# camera.net
KiCad netlist of a schematic drawn in EAGLE
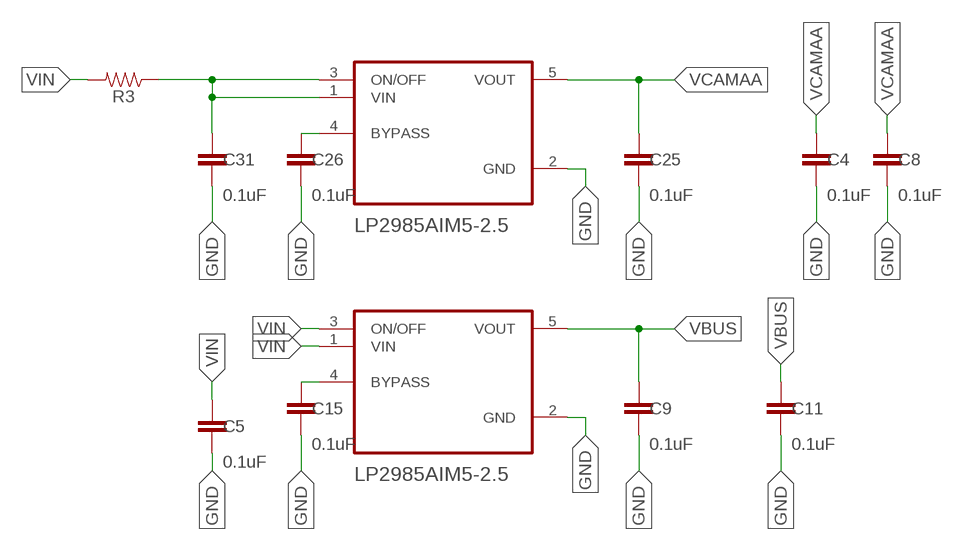
[diagram p0: schematic, sheet 1, part 1 of 3]
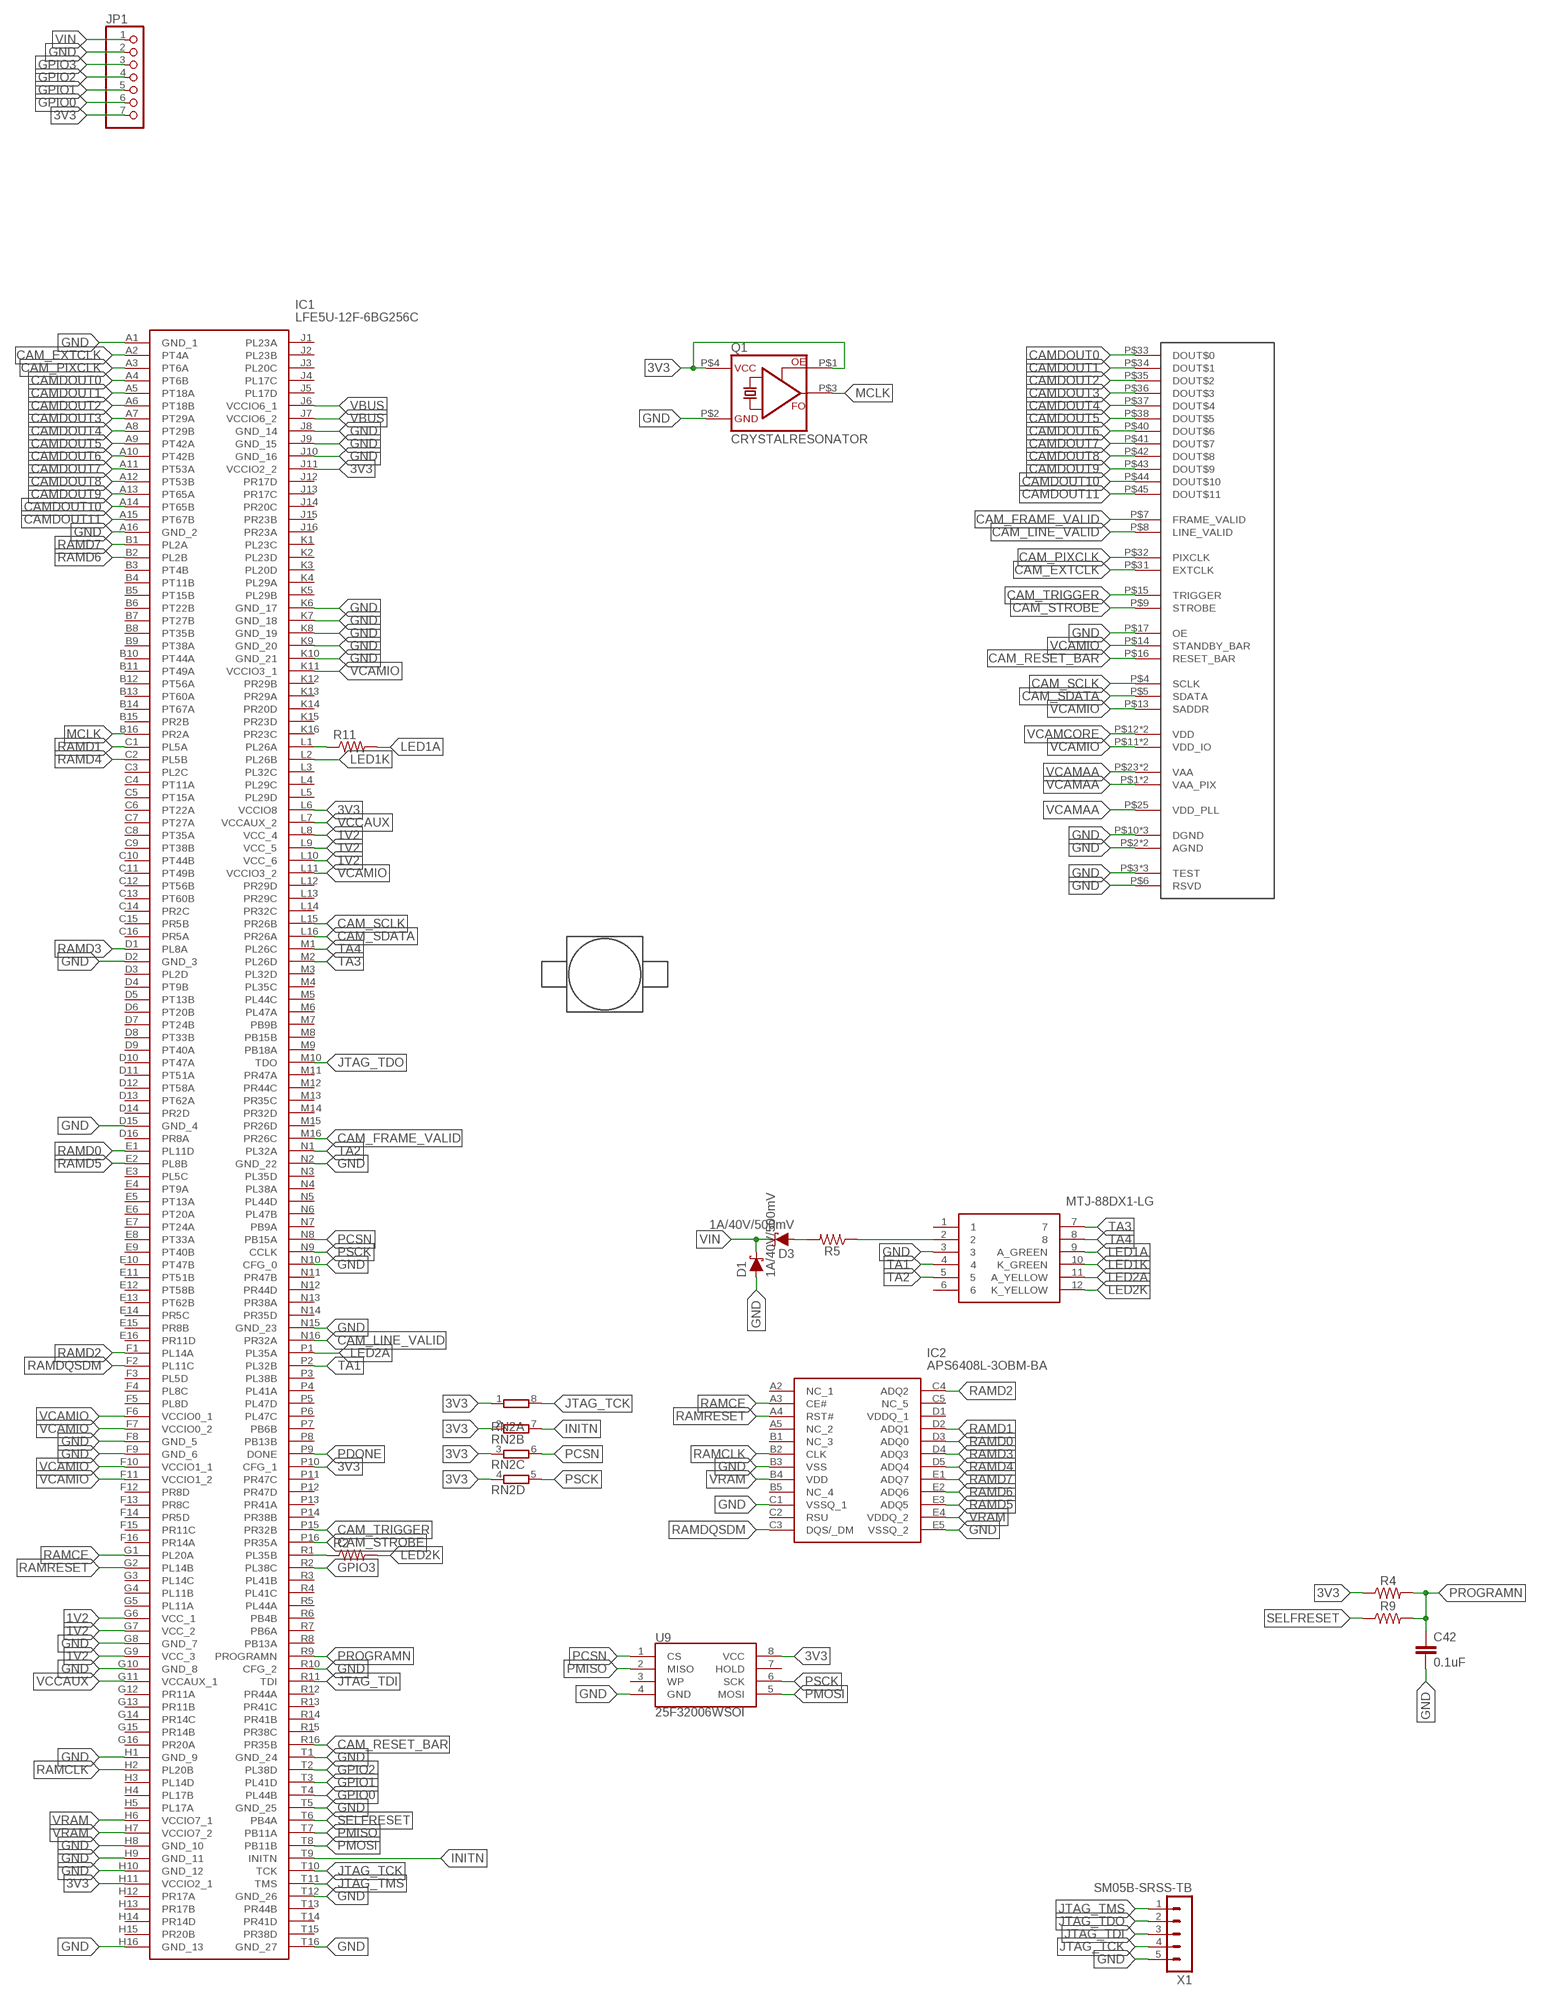
[diagram p1: schematic, sheet 1, part 2 of 3]
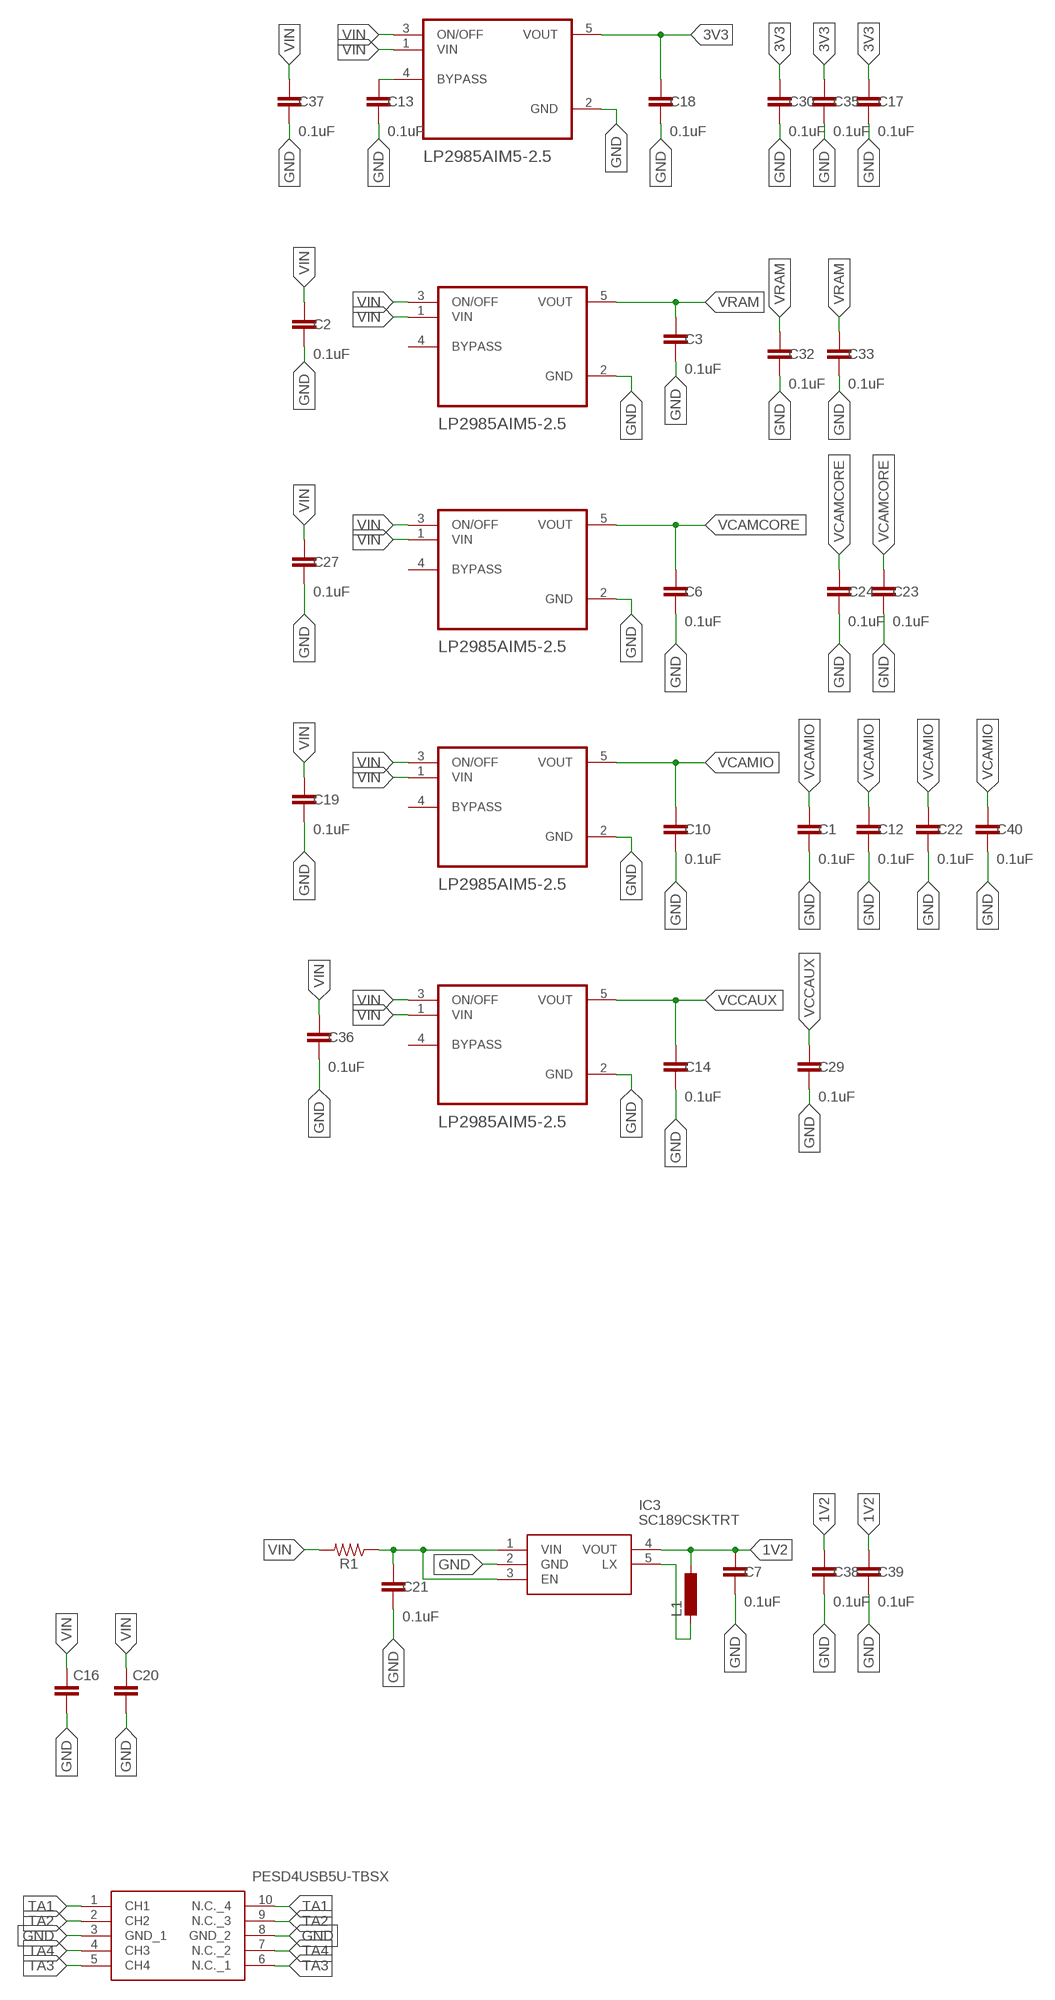
[diagram p2: schematic, sheet 1, part 3 of 3]

(export (version "E")
  (design (tool "Eeschema 10.0.6"))
  (components
    (comp (ref "C1")
      (value "0.1uF")
      (footprint "eagle-import:0603")
      (libsource (lib "eagle-import") (part "0.1UF-0603-25V-5%"))
    )
    (comp (ref "C2")
      (value "0.1uF")
      (footprint "eagle-import:0603")
      (libsource (lib "eagle-import") (part "0.1UF-0603-25V-5%"))
    )
    (comp (ref "C3")
      (value "0.1uF")
      (footprint "eagle-import:0603")
      (libsource (lib "eagle-import") (part "0.1UF-0603-25V-5%"))
    )
    (comp (ref "C4")
      (value "0.1uF")
      (footprint "eagle-import:0603")
      (libsource (lib "eagle-import") (part "0.1UF-0603-25V-5%"))
    )
    (comp (ref "C5")
      (value "0.1uF")
      (footprint "eagle-import:0603")
      (libsource (lib "eagle-import") (part "0.1UF-0603-25V-5%"))
    )
    (comp (ref "C6")
      (value "0.1uF")
      (footprint "eagle-import:0603")
      (libsource (lib "eagle-import") (part "0.1UF-0603-25V-5%"))
    )
    (comp (ref "C7")
      (value "0.1uF")
      (footprint "eagle-import:0603")
      (libsource (lib "eagle-import") (part "0.1UF-0603-25V-5%"))
    )
    (comp (ref "C8")
      (value "0.1uF")
      (footprint "eagle-import:0603")
      (libsource (lib "eagle-import") (part "0.1UF-0603-25V-5%"))
    )
    (comp (ref "C9")
      (value "0.1uF")
      (footprint "eagle-import:0603")
      (libsource (lib "eagle-import") (part "0.1UF-0603-25V-5%"))
    )
    (comp (ref "C10")
      (value "0.1uF")
      (footprint "eagle-import:0603")
      (libsource (lib "eagle-import") (part "0.1UF-0603-25V-5%"))
    )
    (comp (ref "C11")
      (value "0.1uF")
      (footprint "eagle-import:0603")
      (libsource (lib "eagle-import") (part "0.1UF-0603-25V-5%"))
    )
    (comp (ref "C12")
      (value "0.1uF")
      (footprint "eagle-import:0603")
      (libsource (lib "eagle-import") (part "0.1UF-0603-25V-5%"))
    )
    (comp (ref "C13")
      (value "0.1uF")
      (footprint "eagle-import:0603")
      (libsource (lib "eagle-import") (part "0.1UF-0603-25V-5%"))
    )
    (comp (ref "C14")
      (value "0.1uF")
      (footprint "eagle-import:0603")
      (libsource (lib "eagle-import") (part "0.1UF-0603-25V-5%"))
    )
    (comp (ref "C15")
      (value "0.1uF")
      (footprint "eagle-import:0603")
      (libsource (lib "eagle-import") (part "0.1UF-0603-25V-5%"))
    )
    (comp (ref "C16")
      (value "C-EUC1812")
      (footprint "eagle-import:C1812")
      (libsource (lib "eagle-import") (part "C-EUC1812"))
    )
    (comp (ref "C17")
      (value "0.1uF")
      (footprint "eagle-import:0603")
      (libsource (lib "eagle-import") (part "0.1UF-0603-25V-5%"))
    )
    (comp (ref "C18")
      (value "0.1uF")
      (footprint "eagle-import:0603")
      (libsource (lib "eagle-import") (part "0.1UF-0603-25V-5%"))
    )
    (comp (ref "C19")
      (value "0.1uF")
      (footprint "eagle-import:0603")
      (libsource (lib "eagle-import") (part "0.1UF-0603-25V-5%"))
    )
    (comp (ref "C20")
      (value "C-EUC1812")
      (footprint "eagle-import:C1812")
      (libsource (lib "eagle-import") (part "C-EUC1812"))
    )
    (comp (ref "C21")
      (value "0.1uF")
      (footprint "eagle-import:0603")
      (libsource (lib "eagle-import") (part "0.1UF-0603-25V-5%"))
    )
    (comp (ref "C22")
      (value "0.1uF")
      (footprint "eagle-import:0603")
      (libsource (lib "eagle-import") (part "0.1UF-0603-25V-5%"))
    )
    (comp (ref "C23")
      (value "0.1uF")
      (footprint "eagle-import:0603")
      (libsource (lib "eagle-import") (part "0.1UF-0603-25V-5%"))
    )
    (comp (ref "C24")
      (value "0.1uF")
      (footprint "eagle-import:0603")
      (libsource (lib "eagle-import") (part "0.1UF-0603-25V-5%"))
    )
    (comp (ref "C25")
      (value "0.1uF")
      (footprint "eagle-import:0603")
      (libsource (lib "eagle-import") (part "0.1UF-0603-25V-5%"))
    )
    (comp (ref "C26")
      (value "0.1uF")
      (footprint "eagle-import:0603")
      (libsource (lib "eagle-import") (part "0.1UF-0603-25V-5%"))
    )
    (comp (ref "C27")
      (value "0.1uF")
      (footprint "eagle-import:0603")
      (libsource (lib "eagle-import") (part "0.1UF-0603-25V-5%"))
    )
    (comp (ref "C29")
      (value "0.1uF")
      (footprint "eagle-import:0603")
      (libsource (lib "eagle-import") (part "0.1UF-0603-25V-5%"))
    )
    (comp (ref "C30")
      (value "0.1uF")
      (footprint "eagle-import:0603")
      (libsource (lib "eagle-import") (part "0.1UF-0603-25V-5%"))
    )
    (comp (ref "C31")
      (value "0.1uF")
      (footprint "eagle-import:0603")
      (libsource (lib "eagle-import") (part "0.1UF-0603-25V-5%"))
    )
    (comp (ref "C32")
      (value "0.1uF")
      (footprint "eagle-import:0603")
      (libsource (lib "eagle-import") (part "0.1UF-0603-25V-5%"))
    )
    (comp (ref "C33")
      (value "0.1uF")
      (footprint "eagle-import:0603")
      (libsource (lib "eagle-import") (part "0.1UF-0603-25V-5%"))
    )
    (comp (ref "C35")
      (value "0.1uF")
      (footprint "eagle-import:0603")
      (libsource (lib "eagle-import") (part "0.1UF-0603-25V-5%"))
    )
    (comp (ref "C36")
      (value "0.1uF")
      (footprint "eagle-import:0603")
      (libsource (lib "eagle-import") (part "0.1UF-0603-25V-5%"))
    )
    (comp (ref "C37")
      (value "0.1uF")
      (footprint "eagle-import:0603")
      (libsource (lib "eagle-import") (part "0.1UF-0603-25V-5%"))
    )
    (comp (ref "C38")
      (value "0.1uF")
      (footprint "eagle-import:0603")
      (libsource (lib "eagle-import") (part "0.1UF-0603-25V-5%"))
    )
    (comp (ref "C39")
      (value "0.1uF")
      (footprint "eagle-import:0603")
      (libsource (lib "eagle-import") (part "0.1UF-0603-25V-5%"))
    )
    (comp (ref "C40")
      (value "0.1uF")
      (footprint "eagle-import:0603")
      (libsource (lib "eagle-import") (part "0.1UF-0603-25V-5%"))
    )
    (comp (ref "C42")
      (value "0.1uF")
      (footprint "eagle-import:0603")
      (libsource (lib "eagle-import") (part "0.1UF-0603-25V-5%"))
    )
    (comp (ref "D1")
      (value "1A/40V/500mV")
      (footprint "eagle-import:SMA-DIODE")
      (libsource (lib "eagle-import") (part "DIODE-SCHOTTKY-SS14"))
    )
    (comp (ref "D3")
      (value "1A/40V/500mV")
      (footprint "eagle-import:SMA-DIODE")
      (libsource (lib "eagle-import") (part "DIODE-SCHOTTKY-SS14"))
    )
    (comp (ref "D10")
      (value "PESD4USB5U-TBSX")
      (footprint "eagle-import:SON50P100X250X80-10N")
      (fields (field (name "MOUSER_PART_NUMBER") "771-PESD4USB5U-TBSX"))
      (libsource (lib "eagle-import") (part "PESD4USB5U-TBSX"))
    )
    (comp (ref "IC1")
      (value "LFE5U-12F-6BG256C")
      (footprint "eagle-import:BGA256C80P16X16_1400X1400X170")
      (fields (field (name "MF") "Lattice Semiconductor"))
      (libsource (lib "eagle-import") (part "LFE5U-12F-6BG256C"))
    )
    (comp (ref "IC2")
      (value "APS6408L-3OBM-BA")
      (footprint "eagle-import:BGA24C100P5X5_600X800X120")
      (fields (field (name "MOUSER_PART_NUMBER") "878-APS6408L-3OBM-BA"))
      (libsource (lib "eagle-import") (part "APS6408L-3OBM-BA"))
    )
    (comp (ref "IC3")
      (value "SC189CSKTRT")
      (footprint "eagle-import:SOT95P280X145-5N")
      (fields (field (name "MOUSER_PART_NUMBER") "947-SC189CSKTRT"))
      (libsource (lib "eagle-import") (part "SC189CSKTRT"))
    )
    (comp (ref "J1")
      (value "MTJ-88DX1-LG")
      (footprint "eagle-import:MTJ88DX1LG")
      (libsource (lib "eagle-import") (part "MTJ-88DX1-LG"))
    )
    (comp (ref "JP1")
      (value "PINHD-1X7M")
      (footprint "eagle-import:1X07M")
      (libsource (lib "eagle-import") (part "PINHD-1X7M"))
    )
    (comp (ref "L1")
      (value "L-EUL3230M")
      (footprint "eagle-import:L3230M")
      (libsource (lib "eagle-import") (part "L-EUL3230M"))
    )
    (comp (ref "Q1")
      (value "CRYSTALRESONATOR")
      (footprint "eagle-import:XO53X")
      (libsource (lib "eagle-import") (part "CRYSTALRESONATOR"))
    )
    (comp (ref "R1")
      (value "RESISTOR0603")
      (footprint "eagle-import:0603")
      (libsource (lib "eagle-import") (part "RESISTOR0603"))
    )
    (comp (ref "R2")
      (value "RESISTOR0603")
      (footprint "eagle-import:0603")
      (libsource (lib "eagle-import") (part "RESISTOR0603"))
    )
    (comp (ref "R3")
      (value "RESISTOR0603")
      (footprint "eagle-import:0603")
      (libsource (lib "eagle-import") (part "RESISTOR0603"))
    )
    (comp (ref "R4")
      (value "RESISTOR0603")
      (footprint "eagle-import:0603")
      (libsource (lib "eagle-import") (part "RESISTOR0603"))
    )
    (comp (ref "R5")
      (value "RESISTOR0805")
      (footprint "eagle-import:0805")
      (libsource (lib "eagle-import") (part "RESISTOR0805"))
    )
    (comp (ref "R9")
      (value "RESISTOR0603")
      (footprint "eagle-import:0603")
      (libsource (lib "eagle-import") (part "RESISTOR0603"))
    )
    (comp (ref "R11")
      (value "RESISTOR0603")
      (footprint "eagle-import:0603")
      (libsource (lib "eagle-import") (part "RESISTOR0603"))
    )
    (comp (ref "RN2")
      (value "4R-NEXBV8V")
      (footprint "eagle-import:EXBV8V")
      (libsource (lib "eagle-import") (part "4R-NEXBV8V"))
    )
    (comp (ref "U$1")
      (value "LENS-HOLDER")
      (footprint "eagle-import:LENS-HOLDER")
      (libsource (lib "eagle-import") (part "LENS-HOLDER"))
    )
    (comp (ref "U$2")
      (value "MT9P001")
      (footprint "eagle-import:MT9P001")
      (libsource (lib "eagle-import") (part "MT9P001"))
    )
    (comp (ref "U1")
      (value "LP2985AIM5-2.5")
      (footprint "eagle-import:SOT95P280X145-5N")
      (fields (field (name "MF") "Texas Instruments") (field (name "MP") "LP2985AIM5-2.5/NOPB"))
      (libsource (lib "eagle-import") (part "LP2985AIM5-2.5"))
    )
    (comp (ref "U2")
      (value "LP2985AIM5-2.5")
      (footprint "eagle-import:SOT95P280X145-5N")
      (fields (field (name "MF") "Texas Instruments") (field (name "MP") "LP2985AIM5-2.5/NOPB"))
      (libsource (lib "eagle-import") (part "LP2985AIM5-2.5"))
    )
    (comp (ref "U3")
      (value "LP2985AIM5-2.5")
      (footprint "eagle-import:SOT95P280X145-5N")
      (fields (field (name "MF") "Texas Instruments") (field (name "MP") "LP2985AIM5-2.5/NOPB"))
      (libsource (lib "eagle-import") (part "LP2985AIM5-2.5"))
    )
    (comp (ref "U4")
      (value "LP2985AIM5-2.5")
      (footprint "eagle-import:SOT95P280X145-5N")
      (fields (field (name "MF") "Texas Instruments") (field (name "MP") "LP2985AIM5-2.5/NOPB"))
      (libsource (lib "eagle-import") (part "LP2985AIM5-2.5"))
    )
    (comp (ref "U5")
      (value "LP2985AIM5-2.5")
      (footprint "eagle-import:SOT95P280X145-5N")
      (fields (field (name "MF") "Texas Instruments") (field (name "MP") "LP2985AIM5-2.5/NOPB"))
      (libsource (lib "eagle-import") (part "LP2985AIM5-2.5"))
    )
    (comp (ref "U6")
      (value "LP2985AIM5-2.5")
      (footprint "eagle-import:SOT95P280X145-5N")
      (fields (field (name "MF") "Texas Instruments") (field (name "MP") "LP2985AIM5-2.5/NOPB"))
      (libsource (lib "eagle-import") (part "LP2985AIM5-2.5"))
    )
    (comp (ref "U8")
      (value "LP2985AIM5-2.5")
      (footprint "eagle-import:SOT95P280X145-5N")
      (fields (field (name "MF") "Texas Instruments") (field (name "MP") "LP2985AIM5-2.5/NOPB"))
      (libsource (lib "eagle-import") (part "LP2985AIM5-2.5"))
    )
    (comp (ref "U9")
      (value "25F32006WSOI")
      (footprint "eagle-import:SO08-EIAJ")
      (libsource (lib "eagle-import") (part "SPI_FLASH-X25XXSMD1"))
    )
    (comp (ref "X1")
      (value "SM05B-SRSS-TB")
      (footprint "eagle-import:SM05B-SRSS-TB")
      (libsource (lib "eagle-import") (part "SM05B-SRSS-TB"))
    )
  )
  (nets
    (net (code "1") (name "1V2") (class "Default")
      (node (ref "C38") (pin "1") (pinfunction "1_1") (pintype "passive"))
      (node (ref "C39") (pin "1") (pinfunction "1_1") (pintype "passive"))
      (node (ref "C7") (pin "1") (pinfunction "1_1") (pintype "passive"))
      (node (ref "IC1") (pin "G6") (pinfunction "VCC_1_G6") (pintype "bidirectional"))
      (node (ref "IC1") (pin "G7") (pinfunction "VCC_2_G7") (pintype "bidirectional"))
      (node (ref "IC1") (pin "G9") (pinfunction "VCC_3_G9") (pintype "bidirectional"))
      (node (ref "IC1") (pin "L10") (pinfunction "VCC_6_L10") (pintype "bidirectional"))
      (node (ref "IC1") (pin "L8") (pinfunction "VCC_4_L8") (pintype "bidirectional"))
      (node (ref "IC1") (pin "L9") (pinfunction "VCC_5_L9") (pintype "bidirectional"))
      (node (ref "IC3") (pin "4") (pinfunction "VOUT_4") (pintype "bidirectional"))
      (node (ref "L1") (pin "1") (pinfunction "1_1") (pintype "passive"))
    )
    (net (code "2") (name "3V3") (class "Default")
      (node (ref "C17") (pin "1") (pinfunction "1_1") (pintype "passive"))
      (node (ref "C18") (pin "1") (pinfunction "1_1") (pintype "passive"))
      (node (ref "C30") (pin "1") (pinfunction "1_1") (pintype "passive"))
      (node (ref "C35") (pin "1") (pinfunction "1_1") (pintype "passive"))
      (node (ref "IC1") (pin "H11") (pinfunction "VCCIO2_1_H11") (pintype "bidirectional"))
      (node (ref "IC1") (pin "J11") (pinfunction "VCCIO2_2_J11") (pintype "bidirectional"))
      (node (ref "IC1") (pin "L6") (pinfunction "VCCIO8_L6") (pintype "bidirectional"))
      (node (ref "IC1") (pin "P10") (pinfunction "CFG_1_P10") (pintype "bidirectional"))
      (node (ref "JP1") (pin "7") (pinfunction "7_7") (pintype "passive"))
      (node (ref "Q1") (pin "P$1") (pinfunction "OE_P$1") (pintype "input"))
      (node (ref "Q1") (pin "P$4") (pinfunction "VCC_P$4") (pintype "power_in"))
      (node (ref "R4") (pin "1") (pinfunction "1_1") (pintype "passive"))
      (node (ref "RN2") (pin "1") (pinfunction "1_1") (pintype "passive"))
      (node (ref "RN2") (pin "2") (pinfunction "1_2") (pintype "passive"))
      (node (ref "RN2") (pin "3") (pinfunction "1_3") (pintype "passive"))
      (node (ref "RN2") (pin "4") (pinfunction "1_4") (pintype "passive"))
      (node (ref "U2") (pin "5") (pinfunction "VOUT_5") (pintype "output"))
      (node (ref "U9") (pin "8") (pinfunction "VCC_8") (pintype "power_in"))
    )
    (net (code "3") (name "CAMDOUT0") (class "Default")
      (node (ref "IC1") (pin "A4") (pinfunction "PT6B_A4") (pintype "bidirectional"))
      (node (ref "U$2") (pin "P$33") (pinfunction "DOUT$0_P$33") (pintype "output"))
    )
    (net (code "4") (name "CAMDOUT1") (class "Default")
      (node (ref "IC1") (pin "A5") (pinfunction "PT18A_A5") (pintype "bidirectional"))
      (node (ref "U$2") (pin "P$34") (pinfunction "DOUT$1_P$34") (pintype "output"))
    )
    (net (code "5") (name "CAMDOUT2") (class "Default")
      (node (ref "IC1") (pin "A6") (pinfunction "PT18B_A6") (pintype "bidirectional"))
      (node (ref "U$2") (pin "P$35") (pinfunction "DOUT$2_P$35") (pintype "output"))
    )
    (net (code "6") (name "CAMDOUT3") (class "Default")
      (node (ref "IC1") (pin "A7") (pinfunction "PT29A_A7") (pintype "bidirectional"))
      (node (ref "U$2") (pin "P$36") (pinfunction "DOUT$3_P$36") (pintype "output"))
    )
    (net (code "7") (name "CAMDOUT4") (class "Default")
      (node (ref "IC1") (pin "A8") (pinfunction "PT29B_A8") (pintype "bidirectional"))
      (node (ref "U$2") (pin "P$37") (pinfunction "DOUT$4_P$37") (pintype "output"))
    )
    (net (code "8") (name "CAMDOUT5") (class "Default")
      (node (ref "IC1") (pin "A9") (pinfunction "PT42A_A9") (pintype "bidirectional"))
      (node (ref "U$2") (pin "P$38") (pinfunction "DOUT$5_P$38") (pintype "output"))
    )
    (net (code "9") (name "CAMDOUT6") (class "Default")
      (node (ref "IC1") (pin "A10") (pinfunction "PT42B_A10") (pintype "bidirectional"))
      (node (ref "U$2") (pin "P$40") (pinfunction "DOUT$6_P$40") (pintype "output"))
    )
    (net (code "10") (name "CAMDOUT7") (class "Default")
      (node (ref "IC1") (pin "A11") (pinfunction "PT53A_A11") (pintype "bidirectional"))
      (node (ref "U$2") (pin "P$41") (pinfunction "DOUT$7_P$41") (pintype "output"))
    )
    (net (code "11") (name "CAMDOUT8") (class "Default")
      (node (ref "IC1") (pin "A12") (pinfunction "PT53B_A12") (pintype "bidirectional"))
      (node (ref "U$2") (pin "P$42") (pinfunction "DOUT$8_P$42") (pintype "output"))
    )
    (net (code "12") (name "CAMDOUT9") (class "Default")
      (node (ref "IC1") (pin "A13") (pinfunction "PT65A_A13") (pintype "bidirectional"))
      (node (ref "U$2") (pin "P$43") (pinfunction "DOUT$9_P$43") (pintype "output"))
    )
    (net (code "13") (name "CAMDOUT10") (class "Default")
      (node (ref "IC1") (pin "A14") (pinfunction "PT65B_A14") (pintype "bidirectional"))
      (node (ref "U$2") (pin "P$44") (pinfunction "DOUT$10_P$44") (pintype "output"))
    )
    (net (code "14") (name "CAMDOUT11") (class "Default")
      (node (ref "IC1") (pin "A15") (pinfunction "PT67B_A15") (pintype "bidirectional"))
      (node (ref "U$2") (pin "P$45") (pinfunction "DOUT$11_P$45") (pintype "output"))
    )
    (net (code "15") (name "CAM_EXTCLK") (class "Default")
      (node (ref "IC1") (pin "A2") (pinfunction "PT4A_A2") (pintype "bidirectional"))
      (node (ref "U$2") (pin "P$31") (pinfunction "EXTCLK_P$31") (pintype "bidirectional"))
    )
    (net (code "16") (name "CAM_FRAME_VALID") (class "Default")
      (node (ref "IC1") (pin "M16") (pinfunction "PR26C_M16") (pintype "bidirectional"))
      (node (ref "U$2") (pin "P$7") (pinfunction "FRAME_VALID_P$7") (pintype "bidirectional"))
    )
    (net (code "17") (name "CAM_LINE_VALID") (class "Default")
      (node (ref "IC1") (pin "N16") (pinfunction "PR32A_N16") (pintype "bidirectional"))
      (node (ref "U$2") (pin "P$8") (pinfunction "LINE_VALID_P$8") (pintype "bidirectional"))
    )
    (net (code "18") (name "CAM_PIXCLK") (class "Default")
      (node (ref "IC1") (pin "A3") (pinfunction "PT6A_A3") (pintype "bidirectional"))
      (node (ref "U$2") (pin "P$32") (pinfunction "PIXCLK_P$32") (pintype "bidirectional"))
    )
    (net (code "19") (name "CAM_RESET_BAR") (class "Default")
      (node (ref "IC1") (pin "R16") (pinfunction "PR35B_R16") (pintype "bidirectional"))
      (node (ref "U$2") (pin "P$16") (pinfunction "RESET_BAR_P$16") (pintype "bidirectional"))
    )
    (net (code "20") (name "CAM_SCLK") (class "Default")
      (node (ref "IC1") (pin "L15") (pinfunction "PR26B_L15") (pintype "bidirectional"))
      (node (ref "U$2") (pin "P$4") (pinfunction "SCLK_P$4") (pintype "bidirectional"))
    )
    (net (code "21") (name "CAM_SDATA") (class "Default")
      (node (ref "IC1") (pin "L16") (pinfunction "PR26A_L16") (pintype "bidirectional"))
      (node (ref "U$2") (pin "P$5") (pinfunction "SDATA_P$5") (pintype "bidirectional"))
    )
    (net (code "22") (name "CAM_STROBE") (class "Default")
      (node (ref "IC1") (pin "P16") (pinfunction "PR35A_P16") (pintype "bidirectional"))
      (node (ref "U$2") (pin "P$9") (pinfunction "STROBE_P$9") (pintype "bidirectional"))
    )
    (net (code "23") (name "CAM_TRIGGER") (class "Default")
      (node (ref "IC1") (pin "P15") (pinfunction "PR32B_P15") (pintype "bidirectional"))
      (node (ref "U$2") (pin "P$15") (pinfunction "TRIGGER_P$15") (pintype "bidirectional"))
    )
    (net (code "24") (name "GND") (class "Default")
      (node (ref "C1") (pin "2") (pinfunction "2_2") (pintype "passive"))
      (node (ref "C10") (pin "2") (pinfunction "2_2") (pintype "passive"))
      (node (ref "C11") (pin "2") (pinfunction "2_2") (pintype "passive"))
      (node (ref "C12") (pin "2") (pinfunction "2_2") (pintype "passive"))
      (node (ref "C13") (pin "2") (pinfunction "2_2") (pintype "passive"))
      (node (ref "C14") (pin "2") (pinfunction "2_2") (pintype "passive"))
      (node (ref "C15") (pin "2") (pinfunction "2_2") (pintype "passive"))
      (node (ref "C16") (pin "2") (pinfunction "2_2") (pintype "passive"))
      (node (ref "C17") (pin "2") (pinfunction "2_2") (pintype "passive"))
      (node (ref "C18") (pin "2") (pinfunction "2_2") (pintype "passive"))
      (node (ref "C19") (pin "2") (pinfunction "2_2") (pintype "passive"))
      (node (ref "C2") (pin "2") (pinfunction "2_2") (pintype "passive"))
      (node (ref "C20") (pin "2") (pinfunction "2_2") (pintype "passive"))
      (node (ref "C21") (pin "2") (pinfunction "2_2") (pintype "passive"))
      (node (ref "C22") (pin "2") (pinfunction "2_2") (pintype "passive"))
      (node (ref "C23") (pin "2") (pinfunction "2_2") (pintype "passive"))
      (node (ref "C24") (pin "2") (pinfunction "2_2") (pintype "passive"))
      (node (ref "C25") (pin "2") (pinfunction "2_2") (pintype "passive"))
      (node (ref "C26") (pin "2") (pinfunction "2_2") (pintype "passive"))
      (node (ref "C27") (pin "2") (pinfunction "2_2") (pintype "passive"))
      (node (ref "C29") (pin "2") (pinfunction "2_2") (pintype "passive"))
      (node (ref "C3") (pin "2") (pinfunction "2_2") (pintype "passive"))
      (node (ref "C30") (pin "2") (pinfunction "2_2") (pintype "passive"))
      (node (ref "C31") (pin "2") (pinfunction "2_2") (pintype "passive"))
      (node (ref "C32") (pin "2") (pinfunction "2_2") (pintype "passive"))
      (node (ref "C33") (pin "2") (pinfunction "2_2") (pintype "passive"))
      (node (ref "C35") (pin "2") (pinfunction "2_2") (pintype "passive"))
      (node (ref "C36") (pin "2") (pinfunction "2_2") (pintype "passive"))
      (node (ref "C37") (pin "2") (pinfunction "2_2") (pintype "passive"))
      (node (ref "C38") (pin "2") (pinfunction "2_2") (pintype "passive"))
      (node (ref "C39") (pin "2") (pinfunction "2_2") (pintype "passive"))
      (node (ref "C4") (pin "2") (pinfunction "2_2") (pintype "passive"))
      (node (ref "C40") (pin "2") (pinfunction "2_2") (pintype "passive"))
      (node (ref "C42") (pin "2") (pinfunction "2_2") (pintype "passive"))
      (node (ref "C5") (pin "2") (pinfunction "2_2") (pintype "passive"))
      (node (ref "C6") (pin "2") (pinfunction "2_2") (pintype "passive"))
      (node (ref "C7") (pin "2") (pinfunction "2_2") (pintype "passive"))
      (node (ref "C8") (pin "2") (pinfunction "2_2") (pintype "passive"))
      (node (ref "C9") (pin "2") (pinfunction "2_2") (pintype "passive"))
      (node (ref "D1") (pin "A") (pinfunction "A_A") (pintype "passive"))
      (node (ref "D10") (pin "3") (pinfunction "GND_1_3") (pintype "bidirectional"))
      (node (ref "D10") (pin "8") (pinfunction "GND_2_8") (pintype "bidirectional"))
      (node (ref "IC1") (pin "A1") (pinfunction "GND_1_A1") (pintype "bidirectional"))
      (node (ref "IC1") (pin "A16") (pinfunction "GND_2_A16") (pintype "bidirectional"))
      (node (ref "IC1") (pin "D15") (pinfunction "GND_4_D15") (pintype "bidirectional"))
      (node (ref "IC1") (pin "D2") (pinfunction "GND_3_D2") (pintype "bidirectional"))
      (node (ref "IC1") (pin "F8") (pinfunction "GND_5_F8") (pintype "bidirectional"))
      (node (ref "IC1") (pin "F9") (pinfunction "GND_6_F9") (pintype "bidirectional"))
      (node (ref "IC1") (pin "G10") (pinfunction "GND_8_G10") (pintype "bidirectional"))
      (node (ref "IC1") (pin "G8") (pinfunction "GND_7_G8") (pintype "bidirectional"))
      (node (ref "IC1") (pin "H1") (pinfunction "GND_9_H1") (pintype "bidirectional"))
      (node (ref "IC1") (pin "H10") (pinfunction "GND_12_H10") (pintype "bidirectional"))
      (node (ref "IC1") (pin "H16") (pinfunction "GND_13_H16") (pintype "bidirectional"))
      (node (ref "IC1") (pin "H8") (pinfunction "GND_10_H8") (pintype "bidirectional"))
      (node (ref "IC1") (pin "H9") (pinfunction "GND_11_H9") (pintype "bidirectional"))
      (node (ref "IC1") (pin "J10") (pinfunction "GND_16_J10") (pintype "bidirectional"))
      (node (ref "IC1") (pin "J8") (pinfunction "GND_14_J8") (pintype "bidirectional"))
      (node (ref "IC1") (pin "J9") (pinfunction "GND_15_J9") (pintype "bidirectional"))
      (node (ref "IC1") (pin "K10") (pinfunction "GND_21_K10") (pintype "bidirectional"))
      (node (ref "IC1") (pin "K6") (pinfunction "GND_17_K6") (pintype "bidirectional"))
      (node (ref "IC1") (pin "K7") (pinfunction "GND_18_K7") (pintype "bidirectional"))
      (node (ref "IC1") (pin "K8") (pinfunction "GND_19_K8") (pintype "bidirectional"))
      (node (ref "IC1") (pin "K9") (pinfunction "GND_20_K9") (pintype "bidirectional"))
      (node (ref "IC1") (pin "N10") (pinfunction "CFG_0_N10") (pintype "bidirectional"))
      (node (ref "IC1") (pin "N15") (pinfunction "GND_23_N15") (pintype "bidirectional"))
      (node (ref "IC1") (pin "N2") (pinfunction "GND_22_N2") (pintype "bidirectional"))
      (node (ref "IC1") (pin "R10") (pinfunction "CFG_2_R10") (pintype "bidirectional"))
      (node (ref "IC1") (pin "T1") (pinfunction "GND_24_T1") (pintype "bidirectional"))
      (node (ref "IC1") (pin "T12") (pinfunction "GND_26_T12") (pintype "bidirectional"))
      (node (ref "IC1") (pin "T16") (pinfunction "GND_27_T16") (pintype "bidirectional"))
      (node (ref "IC1") (pin "T5") (pinfunction "GND_25_T5") (pintype "bidirectional"))
      (node (ref "IC2") (pin "B3") (pinfunction "VSS_B3") (pintype "bidirectional"))
      (node (ref "IC2") (pin "C1") (pinfunction "VSSQ_1_C1") (pintype "bidirectional"))
      (node (ref "IC2") (pin "E5") (pinfunction "VSSQ_2_E5") (pintype "bidirectional"))
      (node (ref "IC3") (pin "2") (pinfunction "GND_2") (pintype "bidirectional"))
      (node (ref "J1") (pin "3") (pinfunction "3_3") (pintype "bidirectional"))
      (node (ref "JP1") (pin "2") (pinfunction "2_2") (pintype "passive"))
      (node (ref "Q1") (pin "P$2") (pinfunction "GND_P$2") (pintype "power_in"))
      (node (ref "U$2") (pin "P$10") (pinfunction "DGND_P$10") (pintype "bidirectional"))
      (node (ref "U$2") (pin "P$17") (pinfunction "OE_P$17") (pintype "bidirectional"))
      (node (ref "U$2") (pin "P$2") (pinfunction "AGND_P$2") (pintype "bidirectional"))
      (node (ref "U$2") (pin "P$20") (pinfunction "TEST_P$20") (pintype "bidirectional"))
      (node (ref "U$2") (pin "P$21") (pinfunction "TEST_P$21") (pintype "bidirectional"))
      (node (ref "U$2") (pin "P$22") (pinfunction "AGND_P$22") (pintype "bidirectional"))
      (node (ref "U$2") (pin "P$26") (pinfunction "DGND_P$26") (pintype "bidirectional"))
      (node (ref "U$2") (pin "P$3") (pinfunction "TEST_P$3") (pintype "bidirectional"))
      (node (ref "U$2") (pin "P$46") (pinfunction "DGND_P$46") (pintype "bidirectional"))
      (node (ref "U$2") (pin "P$6") (pinfunction "RSVD_P$6") (pintype "bidirectional"))
      (node (ref "U1") (pin "2") (pinfunction "GND_2") (pintype "power_in"))
      (node (ref "U2") (pin "2") (pinfunction "GND_2") (pintype "power_in"))
      (node (ref "U3") (pin "2") (pinfunction "GND_2") (pintype "power_in"))
      (node (ref "U4") (pin "2") (pinfunction "GND_2") (pintype "power_in"))
      (node (ref "U5") (pin "2") (pinfunction "GND_2") (pintype "power_in"))
      (node (ref "U6") (pin "2") (pinfunction "GND_2") (pintype "power_in"))
      (node (ref "U8") (pin "2") (pinfunction "GND_2") (pintype "power_in"))
      (node (ref "U9") (pin "4") (pinfunction "GND_4") (pintype "power_in"))
      (node (ref "X1") (pin "5") (pinfunction "5_5") (pintype "passive"))
    )
    (net (code "25") (name "GPIO0") (class "Default")
      (node (ref "IC1") (pin "T4") (pinfunction "PL44B_T4") (pintype "bidirectional"))
      (node (ref "JP1") (pin "6") (pinfunction "6_6") (pintype "passive"))
    )
    (net (code "26") (name "GPIO1") (class "Default")
      (node (ref "IC1") (pin "T3") (pinfunction "PL41D_T3") (pintype "bidirectional"))
      (node (ref "JP1") (pin "5") (pinfunction "5_5") (pintype "passive"))
    )
    (net (code "27") (name "GPIO2") (class "Default")
      (node (ref "IC1") (pin "T2") (pinfunction "PL38D_T2") (pintype "bidirectional"))
      (node (ref "JP1") (pin "4") (pinfunction "4_4") (pintype "passive"))
    )
    (net (code "28") (name "GPIO3") (class "Default")
      (node (ref "IC1") (pin "R2") (pinfunction "PL38C_R2") (pintype "bidirectional"))
      (node (ref "JP1") (pin "3") (pinfunction "3_3") (pintype "passive"))
    )
    (net (code "29") (name "INITN") (class "Default")
      (node (ref "IC1") (pin "T9") (pinfunction "INITN_T9") (pintype "bidirectional"))
      (node (ref "RN2") (pin "7") (pinfunction "2_7") (pintype "passive"))
    )
    (net (code "30") (name "JTAG_TCK") (class "Default")
      (node (ref "IC1") (pin "T10") (pinfunction "TCK_T10") (pintype "bidirectional"))
      (node (ref "RN2") (pin "8") (pinfunction "2_8") (pintype "passive"))
      (node (ref "X1") (pin "4") (pinfunction "4_4") (pintype "passive"))
    )
    (net (code "31") (name "JTAG_TDI") (class "Default")
      (node (ref "IC1") (pin "R11") (pinfunction "TDI_R11") (pintype "bidirectional"))
      (node (ref "X1") (pin "3") (pinfunction "3_3") (pintype "passive"))
    )
    (net (code "32") (name "JTAG_TDO") (class "Default")
      (node (ref "IC1") (pin "M10") (pinfunction "TDO_M10") (pintype "bidirectional"))
      (node (ref "X1") (pin "2") (pinfunction "2_2") (pintype "passive"))
    )
    (net (code "33") (name "JTAG_TMS") (class "Default")
      (node (ref "IC1") (pin "T11") (pinfunction "TMS_T11") (pintype "bidirectional"))
      (node (ref "X1") (pin "1") (pinfunction "1_1") (pintype "passive"))
    )
    (net (code "34") (name "LED1A") (class "Default")
      (node (ref "J1") (pin "9") (pinfunction "A_GREEN_9") (pintype "bidirectional"))
      (node (ref "R11") (pin "2") (pinfunction "2_2") (pintype "passive"))
    )
    (net (code "35") (name "LED1K") (class "Default")
      (node (ref "IC1") (pin "L2") (pinfunction "PL26B_L2") (pintype "bidirectional"))
      (node (ref "J1") (pin "10") (pinfunction "K_GREEN_10") (pintype "bidirectional"))
    )
    (net (code "36") (name "LED2A") (class "Default")
      (node (ref "IC1") (pin "P1") (pinfunction "PL35A_P1") (pintype "bidirectional"))
      (node (ref "J1") (pin "11") (pinfunction "A_YELLOW_11") (pintype "bidirectional"))
    )
    (net (code "37") (name "LED2K") (class "Default")
      (node (ref "J1") (pin "12") (pinfunction "K_YELLOW_12") (pintype "bidirectional"))
      (node (ref "R2") (pin "2") (pinfunction "2_2") (pintype "passive"))
    )
    (net (code "38") (name "MCLK") (class "Default")
      (node (ref "IC1") (pin "B16") (pinfunction "PR2A_B16") (pintype "bidirectional"))
      (node (ref "Q1") (pin "P$3") (pinfunction "FO_P$3") (pintype "output"))
    )
    (net (code "39") (name "Net-(D3-PadA)") (class "Default")
      (node (ref "D3") (pin "A") (pinfunction "A_A") (pintype "passive"))
      (node (ref "R5") (pin "2") (pinfunction "2_2") (pintype "passive"))
    )
    (net (code "40") (name "Net-(IC1-PL26A)") (class "Default")
      (node (ref "IC1") (pin "L1") (pinfunction "PL26A_L1") (pintype "bidirectional"))
      (node (ref "R11") (pin "1") (pinfunction "1_1") (pintype "passive"))
    )
    (net (code "41") (name "Net-(IC1-PL35B)") (class "Default")
      (node (ref "IC1") (pin "R1") (pinfunction "PL35B_R1") (pintype "bidirectional"))
      (node (ref "R2") (pin "1") (pinfunction "1_1") (pintype "passive"))
    )
    (net (code "42") (name "Net-(IC3-EN)") (class "Default")
      (node (ref "C21") (pin "1") (pinfunction "1_1") (pintype "passive"))
      (node (ref "IC3") (pin "1") (pinfunction "VIN_1") (pintype "bidirectional"))
      (node (ref "IC3") (pin "3") (pinfunction "EN_3") (pintype "bidirectional"))
      (node (ref "R1") (pin "1") (pinfunction "1_1") (pintype "passive"))
    )
    (net (code "43") (name "Net-(IC3-LX)") (class "Default")
      (node (ref "IC3") (pin "5") (pinfunction "LX_5") (pintype "bidirectional"))
      (node (ref "L1") (pin "2") (pinfunction "2_2") (pintype "passive"))
    )
    (net (code "44") (name "Net-(J1-Pad2)") (class "Default")
      (node (ref "J1") (pin "2") (pinfunction "2_2") (pintype "bidirectional"))
      (node (ref "R5") (pin "1") (pinfunction "1_1") (pintype "passive"))
    )
    (net (code "45") (name "Net-(U1-BYPASS)") (class "Default")
      (node (ref "C15") (pin "1") (pinfunction "1_1") (pintype "passive"))
      (node (ref "U1") (pin "4") (pinfunction "BYPASS_4") (pintype "bidirectional"))
    )
    (net (code "46") (name "Net-(U2-BYPASS)") (class "Default")
      (node (ref "C13") (pin "1") (pinfunction "1_1") (pintype "passive"))
      (node (ref "U2") (pin "4") (pinfunction "BYPASS_4") (pintype "bidirectional"))
    )
    (net (code "47") (name "Net-(U8-BYPASS)") (class "Default")
      (node (ref "C26") (pin "1") (pinfunction "1_1") (pintype "passive"))
      (node (ref "U8") (pin "4") (pinfunction "BYPASS_4") (pintype "bidirectional"))
    )
    (net (code "48") (name "Net-(U8-ON{slash}OFF)") (class "Default")
      (node (ref "C31") (pin "1") (pinfunction "1_1") (pintype "passive"))
      (node (ref "R3") (pin "1") (pinfunction "1_1") (pintype "passive"))
      (node (ref "U8") (pin "1") (pinfunction "VIN_1") (pintype "input"))
      (node (ref "U8") (pin "3") (pinfunction "ON/OFF_3") (pintype "input"))
    )
    (net (code "49") (name "PCSN") (class "Default")
      (node (ref "IC1") (pin "N8") (pinfunction "PB15A_N8") (pintype "bidirectional"))
      (node (ref "RN2") (pin "6") (pinfunction "2_6") (pintype "passive"))
      (node (ref "U9") (pin "1") (pinfunction "CS_1") (pintype "bidirectional"))
    )
    (net (code "50") (name "PDONE") (class "Default")
      (node (ref "IC1") (pin "P9") (pinfunction "DONE_P9") (pintype "bidirectional"))
    )
    (net (code "51") (name "PMISO") (class "Default")
      (node (ref "IC1") (pin "T7") (pinfunction "PB11A_T7") (pintype "bidirectional"))
      (node (ref "U9") (pin "2") (pinfunction "MISO_2") (pintype "bidirectional"))
    )
    (net (code "52") (name "PMOSI") (class "Default")
      (node (ref "IC1") (pin "T8") (pinfunction "PB11B_T8") (pintype "bidirectional"))
      (node (ref "U9") (pin "5") (pinfunction "MOSI_5") (pintype "bidirectional"))
    )
    (net (code "53") (name "PROGRAMN") (class "Default")
      (node (ref "C42") (pin "1") (pinfunction "1_1") (pintype "passive"))
      (node (ref "IC1") (pin "R9") (pinfunction "PROGRAMN_R9") (pintype "bidirectional"))
      (node (ref "R4") (pin "2") (pinfunction "2_2") (pintype "passive"))
      (node (ref "R9") (pin "2") (pinfunction "2_2") (pintype "passive"))
    )
    (net (code "54") (name "PSCK") (class "Default")
      (node (ref "IC1") (pin "N9") (pinfunction "CCLK_N9") (pintype "bidirectional"))
      (node (ref "RN2") (pin "5") (pinfunction "2_5") (pintype "passive"))
      (node (ref "U9") (pin "6") (pinfunction "SCK_6") (pintype "bidirectional"))
    )
    (net (code "55") (name "RAMCE") (class "Default")
      (node (ref "IC1") (pin "G1") (pinfunction "PL20A_G1") (pintype "bidirectional"))
      (node (ref "IC2") (pin "A3") (pinfunction "CE#_A3") (pintype "bidirectional"))
    )
    (net (code "56") (name "RAMCLK") (class "Default")
      (node (ref "IC1") (pin "H2") (pinfunction "PL20B_H2") (pintype "bidirectional"))
      (node (ref "IC2") (pin "B2") (pinfunction "CLK_B2") (pintype "bidirectional"))
    )
    (net (code "57") (name "RAMD0") (class "Default")
      (node (ref "IC1") (pin "E1") (pinfunction "PL11D_E1") (pintype "bidirectional"))
      (node (ref "IC2") (pin "D3") (pinfunction "ADQ0_D3") (pintype "bidirectional"))
    )
    (net (code "58") (name "RAMD1") (class "Default")
      (node (ref "IC1") (pin "C1") (pinfunction "PL5A_C1") (pintype "bidirectional"))
      (node (ref "IC2") (pin "D2") (pinfunction "ADQ1_D2") (pintype "bidirectional"))
    )
    (net (code "59") (name "RAMD2") (class "Default")
      (node (ref "IC1") (pin "F1") (pinfunction "PL14A_F1") (pintype "bidirectional"))
      (node (ref "IC2") (pin "C4") (pinfunction "ADQ2_C4") (pintype "bidirectional"))
    )
    (net (code "60") (name "RAMD3") (class "Default")
      (node (ref "IC1") (pin "D1") (pinfunction "PL8A_D1") (pintype "bidirectional"))
      (node (ref "IC2") (pin "D4") (pinfunction "ADQ3_D4") (pintype "bidirectional"))
    )
    (net (code "61") (name "RAMD4") (class "Default")
      (node (ref "IC1") (pin "C2") (pinfunction "PL5B_C2") (pintype "bidirectional"))
      (node (ref "IC2") (pin "D5") (pinfunction "ADQ4_D5") (pintype "bidirectional"))
    )
    (net (code "62") (name "RAMD5") (class "Default")
      (node (ref "IC1") (pin "E2") (pinfunction "PL8B_E2") (pintype "bidirectional"))
      (node (ref "IC2") (pin "E3") (pinfunction "ADQ5_E3") (pintype "bidirectional"))
    )
    (net (code "63") (name "RAMD6") (class "Default")
      (node (ref "IC1") (pin "B2") (pinfunction "PL2B_B2") (pintype "bidirectional"))
      (node (ref "IC2") (pin "E2") (pinfunction "ADQ6_E2") (pintype "bidirectional"))
    )
    (net (code "64") (name "RAMD7") (class "Default")
      (node (ref "IC1") (pin "B1") (pinfunction "PL2A_B1") (pintype "bidirectional"))
      (node (ref "IC2") (pin "E1") (pinfunction "ADQ7_E1") (pintype "bidirectional"))
    )
    (net (code "65") (name "RAMDQSDM") (class "Default")
      (node (ref "IC1") (pin "F2") (pinfunction "PL11C_F2") (pintype "bidirectional"))
      (node (ref "IC2") (pin "C3") (pinfunction "DQS/_DM_C3") (pintype "bidirectional"))
    )
    (net (code "66") (name "RAMRESET") (class "Default")
      (node (ref "IC1") (pin "G2") (pinfunction "PL14B_G2") (pintype "bidirectional"))
      (node (ref "IC2") (pin "A4") (pinfunction "RST#_A4") (pintype "bidirectional"))
    )
    (net (code "67") (name "SELFRESET") (class "Default")
      (node (ref "IC1") (pin "T6") (pinfunction "PB4A_T6") (pintype "bidirectional"))
      (node (ref "R9") (pin "1") (pinfunction "1_1") (pintype "passive"))
    )
    (net (code "68") (name "TA1") (class "Default")
      (node (ref "D10") (pin "1") (pinfunction "CH1_1") (pintype "bidirectional"))
      (node (ref "D10") (pin "10") (pinfunction "N.C._4_10") (pintype "bidirectional"))
      (node (ref "IC1") (pin "P2") (pinfunction "PL32B_P2") (pintype "bidirectional"))
      (node (ref "J1") (pin "4") (pinfunction "4_4") (pintype "bidirectional"))
    )
    (net (code "69") (name "TA2") (class "Default")
      (node (ref "D10") (pin "2") (pinfunction "CH2_2") (pintype "bidirectional"))
      (node (ref "D10") (pin "9") (pinfunction "N.C._3_9") (pintype "bidirectional"))
      (node (ref "IC1") (pin "N1") (pinfunction "PL32A_N1") (pintype "bidirectional"))
      (node (ref "J1") (pin "5") (pinfunction "5_5") (pintype "bidirectional"))
    )
    (net (code "70") (name "TA3") (class "Default")
      (node (ref "D10") (pin "5") (pinfunction "CH4_5") (pintype "bidirectional"))
      (node (ref "D10") (pin "6") (pinfunction "N.C._1_6") (pintype "bidirectional"))
      (node (ref "IC1") (pin "M2") (pinfunction "PL26D_M2") (pintype "bidirectional"))
      (node (ref "J1") (pin "7") (pinfunction "7_7") (pintype "bidirectional"))
    )
    (net (code "71") (name "TA4") (class "Default")
      (node (ref "D10") (pin "4") (pinfunction "CH3_4") (pintype "bidirectional"))
      (node (ref "D10") (pin "7") (pinfunction "N.C._2_7") (pintype "bidirectional"))
      (node (ref "IC1") (pin "M1") (pinfunction "PL26C_M1") (pintype "bidirectional"))
      (node (ref "J1") (pin "8") (pinfunction "8_8") (pintype "bidirectional"))
    )
    (net (code "72") (name "VBUS") (class "Default")
      (node (ref "C11") (pin "1") (pinfunction "1_1") (pintype "passive"))
      (node (ref "C9") (pin "1") (pinfunction "1_1") (pintype "passive"))
      (node (ref "IC1") (pin "J6") (pinfunction "VCCIO6_1_J6") (pintype "bidirectional"))
      (node (ref "IC1") (pin "J7") (pinfunction "VCCIO6_2_J7") (pintype "bidirectional"))
      (node (ref "U1") (pin "5") (pinfunction "VOUT_5") (pintype "output"))
    )
    (net (code "73") (name "VCAMAA") (class "Default")
      (node (ref "C25") (pin "1") (pinfunction "1_1") (pintype "passive"))
      (node (ref "C4") (pin "1") (pinfunction "1_1") (pintype "passive"))
      (node (ref "C8") (pin "1") (pinfunction "1_1") (pintype "passive"))
      (node (ref "U$2") (pin "P$1") (pinfunction "VAA_PIX_P$1") (pintype "bidirectional"))
      (node (ref "U$2") (pin "P$23") (pinfunction "VAA_P$23") (pintype "bidirectional"))
      (node (ref "U$2") (pin "P$24") (pinfunction "VAA_P$24") (pintype "bidirectional"))
      (node (ref "U$2") (pin "P$25") (pinfunction "VDD_PLL_P$25") (pintype "bidirectional"))
      (node (ref "U$2") (pin "P$48") (pinfunction "VAA_PIX_P$48") (pintype "bidirectional"))
      (node (ref "U8") (pin "5") (pinfunction "VOUT_5") (pintype "output"))
    )
    (net (code "74") (name "VCAMCORE") (class "Default")
      (node (ref "C23") (pin "1") (pinfunction "1_1") (pintype "passive"))
      (node (ref "C24") (pin "1") (pinfunction "1_1") (pintype "passive"))
      (node (ref "C6") (pin "1") (pinfunction "1_1") (pintype "passive"))
      (node (ref "U$2") (pin "P$12") (pinfunction "VDD_P$12") (pintype "bidirectional"))
      (node (ref "U$2") (pin "P$47") (pinfunction "VDD_P$47") (pintype "bidirectional"))
      (node (ref "U4") (pin "5") (pinfunction "VOUT_5") (pintype "output"))
    )
    (net (code "75") (name "VCAMIO") (class "Default")
      (node (ref "C1") (pin "1") (pinfunction "1_1") (pintype "passive"))
      (node (ref "C10") (pin "1") (pinfunction "1_1") (pintype "passive"))
      (node (ref "C12") (pin "1") (pinfunction "1_1") (pintype "passive"))
      (node (ref "C22") (pin "1") (pinfunction "1_1") (pintype "passive"))
      (node (ref "C40") (pin "1") (pinfunction "1_1") (pintype "passive"))
      (node (ref "IC1") (pin "F10") (pinfunction "VCCIO1_1_F10") (pintype "bidirectional"))
      (node (ref "IC1") (pin "F11") (pinfunction "VCCIO1_2_F11") (pintype "bidirectional"))
      (node (ref "IC1") (pin "F6") (pinfunction "VCCIO0_1_F6") (pintype "bidirectional"))
      (node (ref "IC1") (pin "F7") (pinfunction "VCCIO0_2_F7") (pintype "bidirectional"))
      (node (ref "IC1") (pin "K11") (pinfunction "VCCIO3_1_K11") (pintype "bidirectional"))
      (node (ref "IC1") (pin "L11") (pinfunction "VCCIO3_2_L11") (pintype "bidirectional"))
      (node (ref "U$2") (pin "P$11") (pinfunction "VDD_IO_P$11") (pintype "bidirectional"))
      (node (ref "U$2") (pin "P$13") (pinfunction "SADDR_P$13") (pintype "bidirectional"))
      (node (ref "U$2") (pin "P$14") (pinfunction "STANDBY_BAR_P$14") (pintype "bidirectional"))
      (node (ref "U$2") (pin "P$39") (pinfunction "VDD_IO_P$39") (pintype "bidirectional"))
      (node (ref "U5") (pin "5") (pinfunction "VOUT_5") (pintype "output"))
    )
    (net (code "76") (name "VCCAUX") (class "Default")
      (node (ref "C14") (pin "1") (pinfunction "1_1") (pintype "passive"))
      (node (ref "C29") (pin "1") (pinfunction "1_1") (pintype "passive"))
      (node (ref "IC1") (pin "G11") (pinfunction "VCCAUX_1_G11") (pintype "bidirectional"))
      (node (ref "IC1") (pin "L7") (pinfunction "VCCAUX_2_L7") (pintype "bidirectional"))
      (node (ref "U6") (pin "5") (pinfunction "VOUT_5") (pintype "output"))
    )
    (net (code "77") (name "VIN") (class "Default")
      (node (ref "C16") (pin "1") (pinfunction "1_1") (pintype "passive"))
      (node (ref "C19") (pin "1") (pinfunction "1_1") (pintype "passive"))
      (node (ref "C2") (pin "1") (pinfunction "1_1") (pintype "passive"))
      (node (ref "C20") (pin "1") (pinfunction "1_1") (pintype "passive"))
      (node (ref "C27") (pin "1") (pinfunction "1_1") (pintype "passive"))
      (node (ref "C36") (pin "1") (pinfunction "1_1") (pintype "passive"))
      (node (ref "C37") (pin "1") (pinfunction "1_1") (pintype "passive"))
      (node (ref "C5") (pin "1") (pinfunction "1_1") (pintype "passive"))
      (node (ref "D1") (pin "C") (pinfunction "C_C") (pintype "passive"))
      (node (ref "D3") (pin "C") (pinfunction "C_C") (pintype "passive"))
      (node (ref "JP1") (pin "1") (pinfunction "1_1") (pintype "passive"))
      (node (ref "R1") (pin "2") (pinfunction "2_2") (pintype "passive"))
      (node (ref "R3") (pin "2") (pinfunction "2_2") (pintype "passive"))
      (node (ref "U1") (pin "1") (pinfunction "VIN_1") (pintype "input"))
      (node (ref "U1") (pin "3") (pinfunction "ON/OFF_3") (pintype "input"))
      (node (ref "U2") (pin "1") (pinfunction "VIN_1") (pintype "input"))
      (node (ref "U2") (pin "3") (pinfunction "ON/OFF_3") (pintype "input"))
      (node (ref "U3") (pin "1") (pinfunction "VIN_1") (pintype "input"))
      (node (ref "U3") (pin "3") (pinfunction "ON/OFF_3") (pintype "input"))
      (node (ref "U4") (pin "1") (pinfunction "VIN_1") (pintype "input"))
      (node (ref "U4") (pin "3") (pinfunction "ON/OFF_3") (pintype "input"))
      (node (ref "U5") (pin "1") (pinfunction "VIN_1") (pintype "input"))
      (node (ref "U5") (pin "3") (pinfunction "ON/OFF_3") (pintype "input"))
      (node (ref "U6") (pin "1") (pinfunction "VIN_1") (pintype "input"))
      (node (ref "U6") (pin "3") (pinfunction "ON/OFF_3") (pintype "input"))
    )
    (net (code "78") (name "VRAM") (class "Default")
      (node (ref "C3") (pin "1") (pinfunction "1_1") (pintype "passive"))
      (node (ref "C32") (pin "1") (pinfunction "1_1") (pintype "passive"))
      (node (ref "C33") (pin "1") (pinfunction "1_1") (pintype "passive"))
      (node (ref "IC1") (pin "H6") (pinfunction "VCCIO7_1_H6") (pintype "bidirectional"))
      (node (ref "IC1") (pin "H7") (pinfunction "VCCIO7_2_H7") (pintype "bidirectional"))
      (node (ref "IC2") (pin "B4") (pinfunction "VDD_B4") (pintype "bidirectional"))
      (node (ref "IC2") (pin "E4") (pinfunction "VDDQ_2_E4") (pintype "bidirectional"))
      (node (ref "U3") (pin "5") (pinfunction "VOUT_5") (pintype "output"))
    )
    (net (code "79") (name "unconnected-(IC1-PB4B-PadR6)") (class "Default")
      (node (ref "IC1") (pin "R6") (pinfunction "PB4B_R6") (pintype "bidirectional"))
    )
    (net (code "80") (name "unconnected-(IC1-PB6A-PadR7)") (class "Default")
      (node (ref "IC1") (pin "R7") (pinfunction "PB6A_R7") (pintype "bidirectional"))
    )
    (net (code "81") (name "unconnected-(IC1-PB6B-PadP7)") (class "Default")
      (node (ref "IC1") (pin "P7") (pinfunction "PB6B_P7") (pintype "bidirectional"))
    )
    (net (code "82") (name "unconnected-(IC1-PB9A-PadN7)") (class "Default")
      (node (ref "IC1") (pin "N7") (pinfunction "PB9A_N7") (pintype "bidirectional"))
    )
    (net (code "83") (name "unconnected-(IC1-PB9B-PadM7)") (class "Default")
      (node (ref "IC1") (pin "M7") (pinfunction "PB9B_M7") (pintype "bidirectional"))
    )
    (net (code "84") (name "unconnected-(IC1-PB13A-PadR8)") (class "Default")
      (node (ref "IC1") (pin "R8") (pinfunction "PB13A_R8") (pintype "bidirectional"))
    )
    (net (code "85") (name "unconnected-(IC1-PB13B-PadP8)") (class "Default")
      (node (ref "IC1") (pin "P8") (pinfunction "PB13B_P8") (pintype "bidirectional"))
    )
    (net (code "86") (name "unconnected-(IC1-PB15B-PadM8)") (class "Default")
      (node (ref "IC1") (pin "M8") (pinfunction "PB15B_M8") (pintype "bidirectional"))
    )
    (net (code "87") (name "unconnected-(IC1-PB18A-PadM9)") (class "Default")
      (node (ref "IC1") (pin "M9") (pinfunction "PB18A_M9") (pintype "bidirectional"))
    )
    (net (code "88") (name "unconnected-(IC1-PL2C-PadC3)") (class "Default")
      (node (ref "IC1") (pin "C3") (pinfunction "PL2C_C3") (pintype "bidirectional"))
    )
    (net (code "89") (name "unconnected-(IC1-PL2D-PadD3)") (class "Default")
      (node (ref "IC1") (pin "D3") (pinfunction "PL2D_D3") (pintype "bidirectional"))
    )
    (net (code "90") (name "unconnected-(IC1-PL5C-PadE3)") (class "Default")
      (node (ref "IC1") (pin "E3") (pinfunction "PL5C_E3") (pintype "bidirectional"))
    )
    (net (code "91") (name "unconnected-(IC1-PL5D-PadF3)") (class "Default")
      (node (ref "IC1") (pin "F3") (pinfunction "PL5D_F3") (pintype "bidirectional"))
    )
    (net (code "92") (name "unconnected-(IC1-PL8C-PadF4)") (class "Default")
      (node (ref "IC1") (pin "F4") (pinfunction "PL8C_F4") (pintype "bidirectional"))
    )
    (net (code "93") (name "unconnected-(IC1-PL8D-PadF5)") (class "Default")
      (node (ref "IC1") (pin "F5") (pinfunction "PL8D_F5") (pintype "bidirectional"))
    )
    (net (code "94") (name "unconnected-(IC1-PL11A-PadG5)") (class "Default")
      (node (ref "IC1") (pin "G5") (pinfunction "PL11A_G5") (pintype "bidirectional"))
    )
    (net (code "95") (name "unconnected-(IC1-PL11B-PadG4)") (class "Default")
      (node (ref "IC1") (pin "G4") (pinfunction "PL11B_G4") (pintype "bidirectional"))
    )
    (net (code "96") (name "unconnected-(IC1-PL14C-PadG3)") (class "Default")
      (node (ref "IC1") (pin "G3") (pinfunction "PL14C_G3") (pintype "bidirectional"))
    )
    (net (code "97") (name "unconnected-(IC1-PL14D-PadH3)") (class "Default")
      (node (ref "IC1") (pin "H3") (pinfunction "PL14D_H3") (pintype "bidirectional"))
    )
    (net (code "98") (name "unconnected-(IC1-PL17A-PadH5)") (class "Default")
      (node (ref "IC1") (pin "H5") (pinfunction "PL17A_H5") (pintype "bidirectional"))
    )
    (net (code "99") (name "unconnected-(IC1-PL17B-PadH4)") (class "Default")
      (node (ref "IC1") (pin "H4") (pinfunction "PL17B_H4") (pintype "bidirectional"))
    )
    (net (code "100") (name "unconnected-(IC1-PL17C-PadJ4)") (class "Default")
      (node (ref "IC1") (pin "J4") (pinfunction "PL17C_J4") (pintype "bidirectional"))
    )
    (net (code "101") (name "unconnected-(IC1-PL17D-PadJ5)") (class "Default")
      (node (ref "IC1") (pin "J5") (pinfunction "PL17D_J5") (pintype "bidirectional"))
    )
    (net (code "102") (name "unconnected-(IC1-PL20C-PadJ3)") (class "Default")
      (node (ref "IC1") (pin "J3") (pinfunction "PL20C_J3") (pintype "bidirectional"))
    )
    (net (code "103") (name "unconnected-(IC1-PL20D-PadK3)") (class "Default")
      (node (ref "IC1") (pin "K3") (pinfunction "PL20D_K3") (pintype "bidirectional"))
    )
    (net (code "104") (name "unconnected-(IC1-PL23A-PadJ1)") (class "Default")
      (node (ref "IC1") (pin "J1") (pinfunction "PL23A_J1") (pintype "bidirectional"))
    )
    (net (code "105") (name "unconnected-(IC1-PL23B-PadJ2)") (class "Default")
      (node (ref "IC1") (pin "J2") (pinfunction "PL23B_J2") (pintype "bidirectional"))
    )
    (net (code "106") (name "unconnected-(IC1-PL23C-PadK1)") (class "Default")
      (node (ref "IC1") (pin "K1") (pinfunction "PL23C_K1") (pintype "bidirectional"))
    )
    (net (code "107") (name "unconnected-(IC1-PL23D-PadK2)") (class "Default")
      (node (ref "IC1") (pin "K2") (pinfunction "PL23D_K2") (pintype "bidirectional"))
    )
    (net (code "108") (name "unconnected-(IC1-PL29A-PadK4)") (class "Default")
      (node (ref "IC1") (pin "K4") (pinfunction "PL29A_K4") (pintype "bidirectional"))
    )
    (net (code "109") (name "unconnected-(IC1-PL29B-PadK5)") (class "Default")
      (node (ref "IC1") (pin "K5") (pinfunction "PL29B_K5") (pintype "bidirectional"))
    )
    (net (code "110") (name "unconnected-(IC1-PL29C-PadL4)") (class "Default")
      (node (ref "IC1") (pin "L4") (pinfunction "PL29C_L4") (pintype "bidirectional"))
    )
    (net (code "111") (name "unconnected-(IC1-PL29D-PadL5)") (class "Default")
      (node (ref "IC1") (pin "L5") (pinfunction "PL29D_L5") (pintype "bidirectional"))
    )
    (net (code "112") (name "unconnected-(IC1-PL32C-PadL3)") (class "Default")
      (node (ref "IC1") (pin "L3") (pinfunction "PL32C_L3") (pintype "bidirectional"))
    )
    (net (code "113") (name "unconnected-(IC1-PL32D-PadM3)") (class "Default")
      (node (ref "IC1") (pin "M3") (pinfunction "PL32D_M3") (pintype "bidirectional"))
    )
    (net (code "114") (name "unconnected-(IC1-PL35C-PadM4)") (class "Default")
      (node (ref "IC1") (pin "M4") (pinfunction "PL35C_M4") (pintype "bidirectional"))
    )
    (net (code "115") (name "unconnected-(IC1-PL35D-PadN3)") (class "Default")
      (node (ref "IC1") (pin "N3") (pinfunction "PL35D_N3") (pintype "bidirectional"))
    )
    (net (code "116") (name "unconnected-(IC1-PL38A-PadN4)") (class "Default")
      (node (ref "IC1") (pin "N4") (pinfunction "PL38A_N4") (pintype "bidirectional"))
    )
    (net (code "117") (name "unconnected-(IC1-PL38B-PadP3)") (class "Default")
      (node (ref "IC1") (pin "P3") (pinfunction "PL38B_P3") (pintype "bidirectional"))
    )
    (net (code "118") (name "unconnected-(IC1-PL41A-PadP4)") (class "Default")
      (node (ref "IC1") (pin "P4") (pinfunction "PL41A_P4") (pintype "bidirectional"))
    )
    (net (code "119") (name "unconnected-(IC1-PL41B-PadR3)") (class "Default")
      (node (ref "IC1") (pin "R3") (pinfunction "PL41B_R3") (pintype "bidirectional"))
    )
    (net (code "120") (name "unconnected-(IC1-PL41C-PadR4)") (class "Default")
      (node (ref "IC1") (pin "R4") (pinfunction "PL41C_R4") (pintype "bidirectional"))
    )
    (net (code "121") (name "unconnected-(IC1-PL44A-PadR5)") (class "Default")
      (node (ref "IC1") (pin "R5") (pinfunction "PL44A_R5") (pintype "bidirectional"))
    )
    (net (code "122") (name "unconnected-(IC1-PL44C-PadM5)") (class "Default")
      (node (ref "IC1") (pin "M5") (pinfunction "PL44C_M5") (pintype "bidirectional"))
    )
    (net (code "123") (name "unconnected-(IC1-PL44D-PadN5)") (class "Default")
      (node (ref "IC1") (pin "N5") (pinfunction "PL44D_N5") (pintype "bidirectional"))
    )
    (net (code "124") (name "unconnected-(IC1-PL47A-PadM6)") (class "Default")
      (node (ref "IC1") (pin "M6") (pinfunction "PL47A_M6") (pintype "bidirectional"))
    )
    (net (code "125") (name "unconnected-(IC1-PL47B-PadN6)") (class "Default")
      (node (ref "IC1") (pin "N6") (pinfunction "PL47B_N6") (pintype "bidirectional"))
    )
    (net (code "126") (name "unconnected-(IC1-PL47C-PadP6)") (class "Default")
      (node (ref "IC1") (pin "P6") (pinfunction "PL47C_P6") (pintype "bidirectional"))
    )
    (net (code "127") (name "unconnected-(IC1-PL47D-PadP5)") (class "Default")
      (node (ref "IC1") (pin "P5") (pinfunction "PL47D_P5") (pintype "bidirectional"))
    )
    (net (code "128") (name "unconnected-(IC1-PR2B-PadB15)") (class "Default")
      (node (ref "IC1") (pin "B15") (pinfunction "PR2B_B15") (pintype "bidirectional"))
    )
    (net (code "129") (name "unconnected-(IC1-PR2C-PadC14)") (class "Default")
      (node (ref "IC1") (pin "C14") (pinfunction "PR2C_C14") (pintype "bidirectional"))
    )
    (net (code "130") (name "unconnected-(IC1-PR2D-PadD14)") (class "Default")
      (node (ref "IC1") (pin "D14") (pinfunction "PR2D_D14") (pintype "bidirectional"))
    )
    (net (code "131") (name "unconnected-(IC1-PR5A-PadC16)") (class "Default")
      (node (ref "IC1") (pin "C16") (pinfunction "PR5A_C16") (pintype "bidirectional"))
    )
    (net (code "132") (name "unconnected-(IC1-PR5B-PadC15)") (class "Default")
      (node (ref "IC1") (pin "C15") (pinfunction "PR5B_C15") (pintype "bidirectional"))
    )
    (net (code "133") (name "unconnected-(IC1-PR5C-PadE14)") (class "Default")
      (node (ref "IC1") (pin "E14") (pinfunction "PR5C_E14") (pintype "bidirectional"))
    )
    (net (code "134") (name "unconnected-(IC1-PR5D-PadF14)") (class "Default")
      (node (ref "IC1") (pin "F14") (pinfunction "PR5D_F14") (pintype "bidirectional"))
    )
    (net (code "135") (name "unconnected-(IC1-PR8A-PadD16)") (class "Default")
      (node (ref "IC1") (pin "D16") (pinfunction "PR8A_D16") (pintype "bidirectional"))
    )
    (net (code "136") (name "unconnected-(IC1-PR8B-PadE15)") (class "Default")
      (node (ref "IC1") (pin "E15") (pinfunction "PR8B_E15") (pintype "bidirectional"))
    )
    (net (code "137") (name "unconnected-(IC1-PR8C-PadF13)") (class "Default")
      (node (ref "IC1") (pin "F13") (pinfunction "PR8C_F13") (pintype "bidirectional"))
    )
    (net (code "138") (name "unconnected-(IC1-PR8D-PadF12)") (class "Default")
      (node (ref "IC1") (pin "F12") (pinfunction "PR8D_F12") (pintype "bidirectional"))
    )
    (net (code "139") (name "unconnected-(IC1-PR11A-PadG12)") (class "Default")
      (node (ref "IC1") (pin "G12") (pinfunction "PR11A_G12") (pintype "bidirectional"))
    )
    (net (code "140") (name "unconnected-(IC1-PR11B-PadG13)") (class "Default")
      (node (ref "IC1") (pin "G13") (pinfunction "PR11B_G13") (pintype "bidirectional"))
    )
    (net (code "141") (name "unconnected-(IC1-PR11C-PadF15)") (class "Default")
      (node (ref "IC1") (pin "F15") (pinfunction "PR11C_F15") (pintype "bidirectional"))
    )
    (net (code "142") (name "unconnected-(IC1-PR11D-PadE16)") (class "Default")
      (node (ref "IC1") (pin "E16") (pinfunction "PR11D_E16") (pintype "bidirectional"))
    )
    (net (code "143") (name "unconnected-(IC1-PR14A-PadF16)") (class "Default")
      (node (ref "IC1") (pin "F16") (pinfunction "PR14A_F16") (pintype "bidirectional"))
    )
    (net (code "144") (name "unconnected-(IC1-PR14B-PadG15)") (class "Default")
      (node (ref "IC1") (pin "G15") (pinfunction "PR14B_G15") (pintype "bidirectional"))
    )
    (net (code "145") (name "unconnected-(IC1-PR14C-PadG14)") (class "Default")
      (node (ref "IC1") (pin "G14") (pinfunction "PR14C_G14") (pintype "bidirectional"))
    )
    (net (code "146") (name "unconnected-(IC1-PR14D-PadH14)") (class "Default")
      (node (ref "IC1") (pin "H14") (pinfunction "PR14D_H14") (pintype "bidirectional"))
    )
    (net (code "147") (name "unconnected-(IC1-PR17A-PadH12)") (class "Default")
      (node (ref "IC1") (pin "H12") (pinfunction "PR17A_H12") (pintype "bidirectional"))
    )
    (net (code "148") (name "unconnected-(IC1-PR17B-PadH13)") (class "Default")
      (node (ref "IC1") (pin "H13") (pinfunction "PR17B_H13") (pintype "bidirectional"))
    )
    (net (code "149") (name "unconnected-(IC1-PR17C-PadJ13)") (class "Default")
      (node (ref "IC1") (pin "J13") (pinfunction "PR17C_J13") (pintype "bidirectional"))
    )
    (net (code "150") (name "unconnected-(IC1-PR17D-PadJ12)") (class "Default")
      (node (ref "IC1") (pin "J12") (pinfunction "PR17D_J12") (pintype "bidirectional"))
    )
    (net (code "151") (name "unconnected-(IC1-PR20A-PadG16)") (class "Default")
      (node (ref "IC1") (pin "G16") (pinfunction "PR20A_G16") (pintype "bidirectional"))
    )
    (net (code "152") (name "unconnected-(IC1-PR20B-PadH15)") (class "Default")
      (node (ref "IC1") (pin "H15") (pinfunction "PR20B_H15") (pintype "bidirectional"))
    )
    (net (code "153") (name "unconnected-(IC1-PR20C-PadJ14)") (class "Default")
      (node (ref "IC1") (pin "J14") (pinfunction "PR20C_J14") (pintype "bidirectional"))
    )
    (net (code "154") (name "unconnected-(IC1-PR20D-PadK14)") (class "Default")
      (node (ref "IC1") (pin "K14") (pinfunction "PR20D_K14") (pintype "bidirectional"))
    )
    (net (code "155") (name "unconnected-(IC1-PR23A-PadJ16)") (class "Default")
      (node (ref "IC1") (pin "J16") (pinfunction "PR23A_J16") (pintype "bidirectional"))
    )
    (net (code "156") (name "unconnected-(IC1-PR23B-PadJ15)") (class "Default")
      (node (ref "IC1") (pin "J15") (pinfunction "PR23B_J15") (pintype "bidirectional"))
    )
    (net (code "157") (name "unconnected-(IC1-PR23C-PadK16)") (class "Default")
      (node (ref "IC1") (pin "K16") (pinfunction "PR23C_K16") (pintype "bidirectional"))
    )
    (net (code "158") (name "unconnected-(IC1-PR23D-PadK15)") (class "Default")
      (node (ref "IC1") (pin "K15") (pinfunction "PR23D_K15") (pintype "bidirectional"))
    )
    (net (code "159") (name "unconnected-(IC1-PR26D-PadM15)") (class "Default")
      (node (ref "IC1") (pin "M15") (pinfunction "PR26D_M15") (pintype "bidirectional"))
    )
    (net (code "160") (name "unconnected-(IC1-PR29A-PadK13)") (class "Default")
      (node (ref "IC1") (pin "K13") (pinfunction "PR29A_K13") (pintype "bidirectional"))
    )
    (net (code "161") (name "unconnected-(IC1-PR29B-PadK12)") (class "Default")
      (node (ref "IC1") (pin "K12") (pinfunction "PR29B_K12") (pintype "bidirectional"))
    )
    (net (code "162") (name "unconnected-(IC1-PR29C-PadL13)") (class "Default")
      (node (ref "IC1") (pin "L13") (pinfunction "PR29C_L13") (pintype "bidirectional"))
    )
    (net (code "163") (name "unconnected-(IC1-PR29D-PadL12)") (class "Default")
      (node (ref "IC1") (pin "L12") (pinfunction "PR29D_L12") (pintype "bidirectional"))
    )
    (net (code "164") (name "unconnected-(IC1-PR32C-PadL14)") (class "Default")
      (node (ref "IC1") (pin "L14") (pinfunction "PR32C_L14") (pintype "bidirectional"))
    )
    (net (code "165") (name "unconnected-(IC1-PR32D-PadM14)") (class "Default")
      (node (ref "IC1") (pin "M14") (pinfunction "PR32D_M14") (pintype "bidirectional"))
    )
    (net (code "166") (name "unconnected-(IC1-PR35C-PadM13)") (class "Default")
      (node (ref "IC1") (pin "M13") (pinfunction "PR35C_M13") (pintype "bidirectional"))
    )
    (net (code "167") (name "unconnected-(IC1-PR35D-PadN14)") (class "Default")
      (node (ref "IC1") (pin "N14") (pinfunction "PR35D_N14") (pintype "bidirectional"))
    )
    (net (code "168") (name "unconnected-(IC1-PR38A-PadN13)") (class "Default")
      (node (ref "IC1") (pin "N13") (pinfunction "PR38A_N13") (pintype "bidirectional"))
    )
    (net (code "169") (name "unconnected-(IC1-PR38B-PadP14)") (class "Default")
      (node (ref "IC1") (pin "P14") (pinfunction "PR38B_P14") (pintype "bidirectional"))
    )
    (net (code "170") (name "unconnected-(IC1-PR38C-PadR15)") (class "Default")
      (node (ref "IC1") (pin "R15") (pinfunction "PR38C_R15") (pintype "bidirectional"))
    )
    (net (code "171") (name "unconnected-(IC1-PR38D-PadT15)") (class "Default")
      (node (ref "IC1") (pin "T15") (pinfunction "PR38D_T15") (pintype "bidirectional"))
    )
    (net (code "172") (name "unconnected-(IC1-PR41A-PadP13)") (class "Default")
      (node (ref "IC1") (pin "P13") (pinfunction "PR41A_P13") (pintype "bidirectional"))
    )
    (net (code "173") (name "unconnected-(IC1-PR41B-PadR14)") (class "Default")
      (node (ref "IC1") (pin "R14") (pinfunction "PR41B_R14") (pintype "bidirectional"))
    )
    (net (code "174") (name "unconnected-(IC1-PR41C-PadR13)") (class "Default")
      (node (ref "IC1") (pin "R13") (pinfunction "PR41C_R13") (pintype "bidirectional"))
    )
    (net (code "175") (name "unconnected-(IC1-PR41D-PadT14)") (class "Default")
      (node (ref "IC1") (pin "T14") (pinfunction "PR41D_T14") (pintype "bidirectional"))
    )
    (net (code "176") (name "unconnected-(IC1-PR44A-PadR12)") (class "Default")
      (node (ref "IC1") (pin "R12") (pinfunction "PR44A_R12") (pintype "bidirectional"))
    )
    (net (code "177") (name "unconnected-(IC1-PR44B-PadT13)") (class "Default")
      (node (ref "IC1") (pin "T13") (pinfunction "PR44B_T13") (pintype "bidirectional"))
    )
    (net (code "178") (name "unconnected-(IC1-PR44C-PadM12)") (class "Default")
      (node (ref "IC1") (pin "M12") (pinfunction "PR44C_M12") (pintype "bidirectional"))
    )
    (net (code "179") (name "unconnected-(IC1-PR44D-PadN12)") (class "Default")
      (node (ref "IC1") (pin "N12") (pinfunction "PR44D_N12") (pintype "bidirectional"))
    )
    (net (code "180") (name "unconnected-(IC1-PR47A-PadM11)") (class "Default")
      (node (ref "IC1") (pin "M11") (pinfunction "PR47A_M11") (pintype "bidirectional"))
    )
    (net (code "181") (name "unconnected-(IC1-PR47B-PadN11)") (class "Default")
      (node (ref "IC1") (pin "N11") (pinfunction "PR47B_N11") (pintype "bidirectional"))
    )
    (net (code "182") (name "unconnected-(IC1-PR47C-PadP11)") (class "Default")
      (node (ref "IC1") (pin "P11") (pinfunction "PR47C_P11") (pintype "bidirectional"))
    )
    (net (code "183") (name "unconnected-(IC1-PR47D-PadP12)") (class "Default")
      (node (ref "IC1") (pin "P12") (pinfunction "PR47D_P12") (pintype "bidirectional"))
    )
    (net (code "184") (name "unconnected-(IC1-PT4B-PadB3)") (class "Default")
      (node (ref "IC1") (pin "B3") (pinfunction "PT4B_B3") (pintype "bidirectional"))
    )
    (net (code "185") (name "unconnected-(IC1-PT9A-PadE4)") (class "Default")
      (node (ref "IC1") (pin "E4") (pinfunction "PT9A_E4") (pintype "bidirectional"))
    )
    (net (code "186") (name "unconnected-(IC1-PT9B-PadD4)") (class "Default")
      (node (ref "IC1") (pin "D4") (pinfunction "PT9B_D4") (pintype "bidirectional"))
    )
    (net (code "187") (name "unconnected-(IC1-PT11A-PadC4)") (class "Default")
      (node (ref "IC1") (pin "C4") (pinfunction "PT11A_C4") (pintype "bidirectional"))
    )
    (net (code "188") (name "unconnected-(IC1-PT11B-PadB4)") (class "Default")
      (node (ref "IC1") (pin "B4") (pinfunction "PT11B_B4") (pintype "bidirectional"))
    )
    (net (code "189") (name "unconnected-(IC1-PT13A-PadE5)") (class "Default")
      (node (ref "IC1") (pin "E5") (pinfunction "PT13A_E5") (pintype "bidirectional"))
    )
    (net (code "190") (name "unconnected-(IC1-PT13B-PadD5)") (class "Default")
      (node (ref "IC1") (pin "D5") (pinfunction "PT13B_D5") (pintype "bidirectional"))
    )
    (net (code "191") (name "unconnected-(IC1-PT15A-PadC5)") (class "Default")
      (node (ref "IC1") (pin "C5") (pinfunction "PT15A_C5") (pintype "bidirectional"))
    )
    (net (code "192") (name "unconnected-(IC1-PT15B-PadB5)") (class "Default")
      (node (ref "IC1") (pin "B5") (pinfunction "PT15B_B5") (pintype "bidirectional"))
    )
    (net (code "193") (name "unconnected-(IC1-PT20A-PadE6)") (class "Default")
      (node (ref "IC1") (pin "E6") (pinfunction "PT20A_E6") (pintype "bidirectional"))
    )
    (net (code "194") (name "unconnected-(IC1-PT20B-PadD6)") (class "Default")
      (node (ref "IC1") (pin "D6") (pinfunction "PT20B_D6") (pintype "bidirectional"))
    )
    (net (code "195") (name "unconnected-(IC1-PT22A-PadC6)") (class "Default")
      (node (ref "IC1") (pin "C6") (pinfunction "PT22A_C6") (pintype "bidirectional"))
    )
    (net (code "196") (name "unconnected-(IC1-PT22B-PadB6)") (class "Default")
      (node (ref "IC1") (pin "B6") (pinfunction "PT22B_B6") (pintype "bidirectional"))
    )
    (net (code "197") (name "unconnected-(IC1-PT24A-PadE7)") (class "Default")
      (node (ref "IC1") (pin "E7") (pinfunction "PT24A_E7") (pintype "bidirectional"))
    )
    (net (code "198") (name "unconnected-(IC1-PT24B-PadD7)") (class "Default")
      (node (ref "IC1") (pin "D7") (pinfunction "PT24B_D7") (pintype "bidirectional"))
    )
    (net (code "199") (name "unconnected-(IC1-PT27A-PadC7)") (class "Default")
      (node (ref "IC1") (pin "C7") (pinfunction "PT27A_C7") (pintype "bidirectional"))
    )
    (net (code "200") (name "unconnected-(IC1-PT27B-PadB7)") (class "Default")
      (node (ref "IC1") (pin "B7") (pinfunction "PT27B_B7") (pintype "bidirectional"))
    )
    (net (code "201") (name "unconnected-(IC1-PT33A-PadE8)") (class "Default")
      (node (ref "IC1") (pin "E8") (pinfunction "PT33A_E8") (pintype "bidirectional"))
    )
    (net (code "202") (name "unconnected-(IC1-PT33B-PadD8)") (class "Default")
      (node (ref "IC1") (pin "D8") (pinfunction "PT33B_D8") (pintype "bidirectional"))
    )
    (net (code "203") (name "unconnected-(IC1-PT35A-PadC8)") (class "Default")
      (node (ref "IC1") (pin "C8") (pinfunction "PT35A_C8") (pintype "bidirectional"))
    )
    (net (code "204") (name "unconnected-(IC1-PT35B-PadB8)") (class "Default")
      (node (ref "IC1") (pin "B8") (pinfunction "PT35B_B8") (pintype "bidirectional"))
    )
    (net (code "205") (name "unconnected-(IC1-PT38A-PadB9)") (class "Default")
      (node (ref "IC1") (pin "B9") (pinfunction "PT38A_B9") (pintype "bidirectional"))
    )
    (net (code "206") (name "unconnected-(IC1-PT38B-PadC9)") (class "Default")
      (node (ref "IC1") (pin "C9") (pinfunction "PT38B_C9") (pintype "bidirectional"))
    )
    (net (code "207") (name "unconnected-(IC1-PT40A-PadD9)") (class "Default")
      (node (ref "IC1") (pin "D9") (pinfunction "PT40A_D9") (pintype "bidirectional"))
    )
    (net (code "208") (name "unconnected-(IC1-PT40B-PadE9)") (class "Default")
      (node (ref "IC1") (pin "E9") (pinfunction "PT40B_E9") (pintype "bidirectional"))
    )
    (net (code "209") (name "unconnected-(IC1-PT44A-PadB10)") (class "Default")
      (node (ref "IC1") (pin "B10") (pinfunction "PT44A_B10") (pintype "bidirectional"))
    )
    (net (code "210") (name "unconnected-(IC1-PT44B-PadC10)") (class "Default")
      (node (ref "IC1") (pin "C10") (pinfunction "PT44B_C10") (pintype "bidirectional"))
    )
    (net (code "211") (name "unconnected-(IC1-PT47A-PadD10)") (class "Default")
      (node (ref "IC1") (pin "D10") (pinfunction "PT47A_D10") (pintype "bidirectional"))
    )
    (net (code "212") (name "unconnected-(IC1-PT47B-PadE10)") (class "Default")
      (node (ref "IC1") (pin "E10") (pinfunction "PT47B_E10") (pintype "bidirectional"))
    )
    (net (code "213") (name "unconnected-(IC1-PT49A-PadB11)") (class "Default")
      (node (ref "IC1") (pin "B11") (pinfunction "PT49A_B11") (pintype "bidirectional"))
    )
    (net (code "214") (name "unconnected-(IC1-PT49B-PadC11)") (class "Default")
      (node (ref "IC1") (pin "C11") (pinfunction "PT49B_C11") (pintype "bidirectional"))
    )
    (net (code "215") (name "unconnected-(IC1-PT51A-PadD11)") (class "Default")
      (node (ref "IC1") (pin "D11") (pinfunction "PT51A_D11") (pintype "bidirectional"))
    )
    (net (code "216") (name "unconnected-(IC1-PT51B-PadE11)") (class "Default")
      (node (ref "IC1") (pin "E11") (pinfunction "PT51B_E11") (pintype "bidirectional"))
    )
    (net (code "217") (name "unconnected-(IC1-PT56A-PadB12)") (class "Default")
      (node (ref "IC1") (pin "B12") (pinfunction "PT56A_B12") (pintype "bidirectional"))
    )
    (net (code "218") (name "unconnected-(IC1-PT56B-PadC12)") (class "Default")
      (node (ref "IC1") (pin "C12") (pinfunction "PT56B_C12") (pintype "bidirectional"))
    )
    (net (code "219") (name "unconnected-(IC1-PT58A-PadD12)") (class "Default")
      (node (ref "IC1") (pin "D12") (pinfunction "PT58A_D12") (pintype "bidirectional"))
    )
    (net (code "220") (name "unconnected-(IC1-PT58B-PadE12)") (class "Default")
      (node (ref "IC1") (pin "E12") (pinfunction "PT58B_E12") (pintype "bidirectional"))
    )
    (net (code "221") (name "unconnected-(IC1-PT60A-PadB13)") (class "Default")
      (node (ref "IC1") (pin "B13") (pinfunction "PT60A_B13") (pintype "bidirectional"))
    )
    (net (code "222") (name "unconnected-(IC1-PT60B-PadC13)") (class "Default")
      (node (ref "IC1") (pin "C13") (pinfunction "PT60B_C13") (pintype "bidirectional"))
    )
    (net (code "223") (name "unconnected-(IC1-PT62A-PadD13)") (class "Default")
      (node (ref "IC1") (pin "D13") (pinfunction "PT62A_D13") (pintype "bidirectional"))
    )
    (net (code "224") (name "unconnected-(IC1-PT62B-PadE13)") (class "Default")
      (node (ref "IC1") (pin "E13") (pinfunction "PT62B_E13") (pintype "bidirectional"))
    )
    (net (code "225") (name "unconnected-(IC1-PT67A-PadB14)") (class "Default")
      (node (ref "IC1") (pin "B14") (pinfunction "PT67A_B14") (pintype "bidirectional"))
    )
    (net (code "226") (name "unconnected-(IC2-NC_1-PadA2)") (class "Default")
      (node (ref "IC2") (pin "A2") (pinfunction "NC_1_A2") (pintype "bidirectional"))
    )
    (net (code "227") (name "unconnected-(IC2-NC_2-PadA5)") (class "Default")
      (node (ref "IC2") (pin "A5") (pinfunction "NC_2_A5") (pintype "bidirectional"))
    )
    (net (code "228") (name "unconnected-(IC2-NC_3-PadB1)") (class "Default")
      (node (ref "IC2") (pin "B1") (pinfunction "NC_3_B1") (pintype "bidirectional"))
    )
    (net (code "229") (name "unconnected-(IC2-NC_4-PadB5)") (class "Default")
      (node (ref "IC2") (pin "B5") (pinfunction "NC_4_B5") (pintype "bidirectional"))
    )
    (net (code "230") (name "unconnected-(IC2-NC_5-PadC5)") (class "Default")
      (node (ref "IC2") (pin "C5") (pinfunction "NC_5_C5") (pintype "bidirectional"))
    )
    (net (code "231") (name "unconnected-(IC2-RSU-PadC2)") (class "Default")
      (node (ref "IC2") (pin "C2") (pinfunction "RSU_C2") (pintype "bidirectional"))
    )
    (net (code "232") (name "unconnected-(IC2-VDDQ_1-PadD1)") (class "Default")
      (node (ref "IC2") (pin "D1") (pinfunction "VDDQ_1_D1") (pintype "bidirectional"))
    )
    (net (code "233") (name "unconnected-(J1-Pad1)") (class "Default")
      (node (ref "J1") (pin "1") (pinfunction "1_1") (pintype "bidirectional"))
    )
    (net (code "234") (name "unconnected-(J1-Pad6)") (class "Default")
      (node (ref "J1") (pin "6") (pinfunction "6_6") (pintype "bidirectional"))
    )
    (net (code "235") (name "unconnected-(U3-BYPASS-Pad4)") (class "Default")
      (node (ref "U3") (pin "4") (pinfunction "BYPASS_4") (pintype "bidirectional"))
    )
    (net (code "236") (name "unconnected-(U4-BYPASS-Pad4)") (class "Default")
      (node (ref "U4") (pin "4") (pinfunction "BYPASS_4") (pintype "bidirectional"))
    )
    (net (code "237") (name "unconnected-(U5-BYPASS-Pad4)") (class "Default")
      (node (ref "U5") (pin "4") (pinfunction "BYPASS_4") (pintype "bidirectional"))
    )
    (net (code "238") (name "unconnected-(U6-BYPASS-Pad4)") (class "Default")
      (node (ref "U6") (pin "4") (pinfunction "BYPASS_4") (pintype "bidirectional"))
    )
    (net (code "239") (name "unconnected-(U9-HOLD-Pad7)") (class "Default")
      (node (ref "U9") (pin "7") (pinfunction "HOLD_7") (pintype "bidirectional"))
    )
    (net (code "240") (name "unconnected-(U9-WP-Pad3)") (class "Default")
      (node (ref "U9") (pin "3") (pinfunction "WP_3") (pintype "bidirectional"))
    )
  )
)
